# GDPHS_VGA_-_v2_2_1.net
KiCad netlist of a schematic drawn in EAGLE
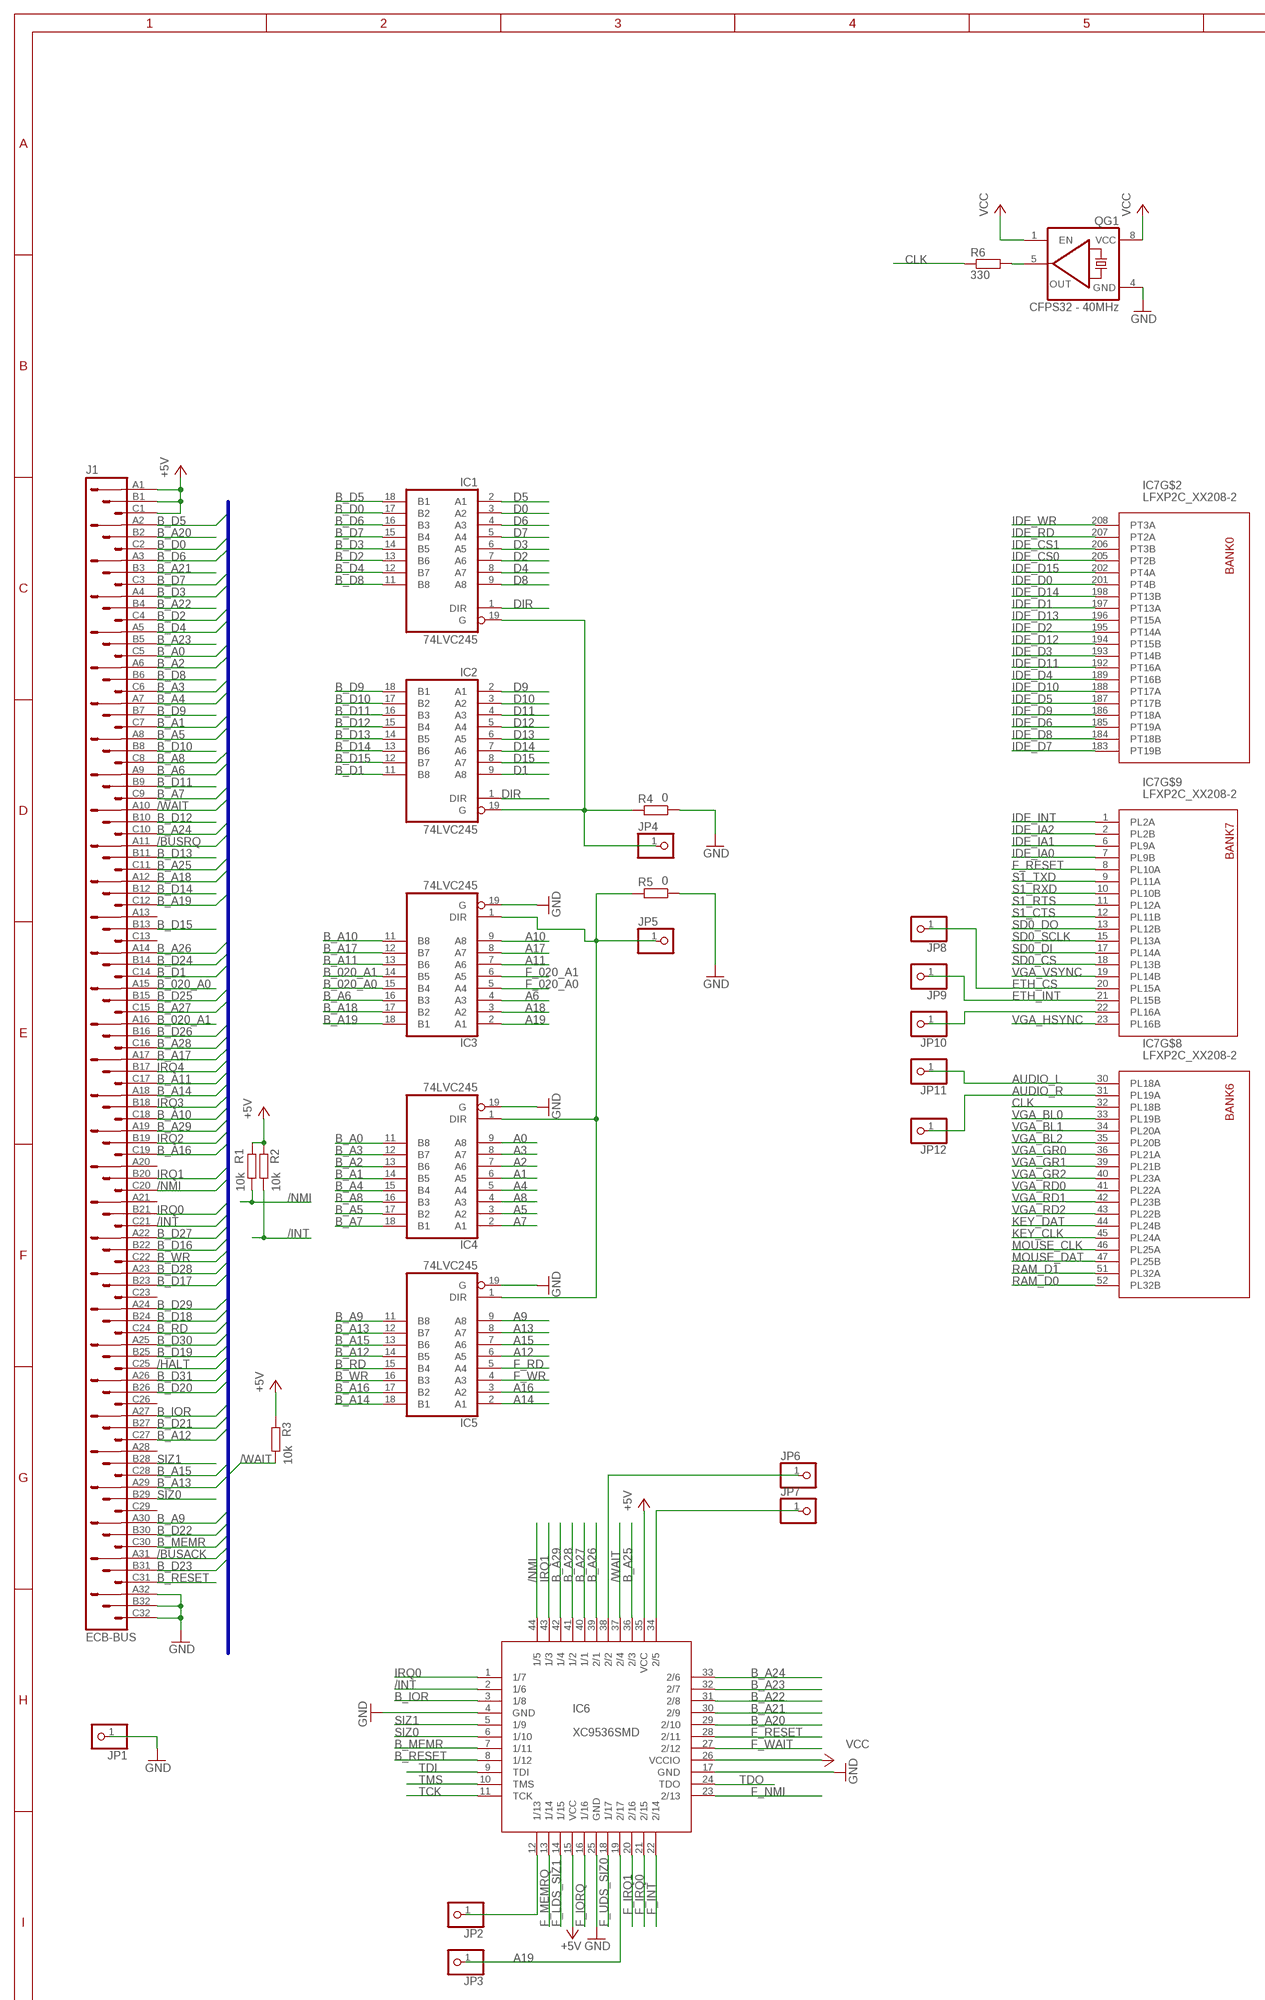
[diagram p0: schematic, sheet 1, part 1 of 2]
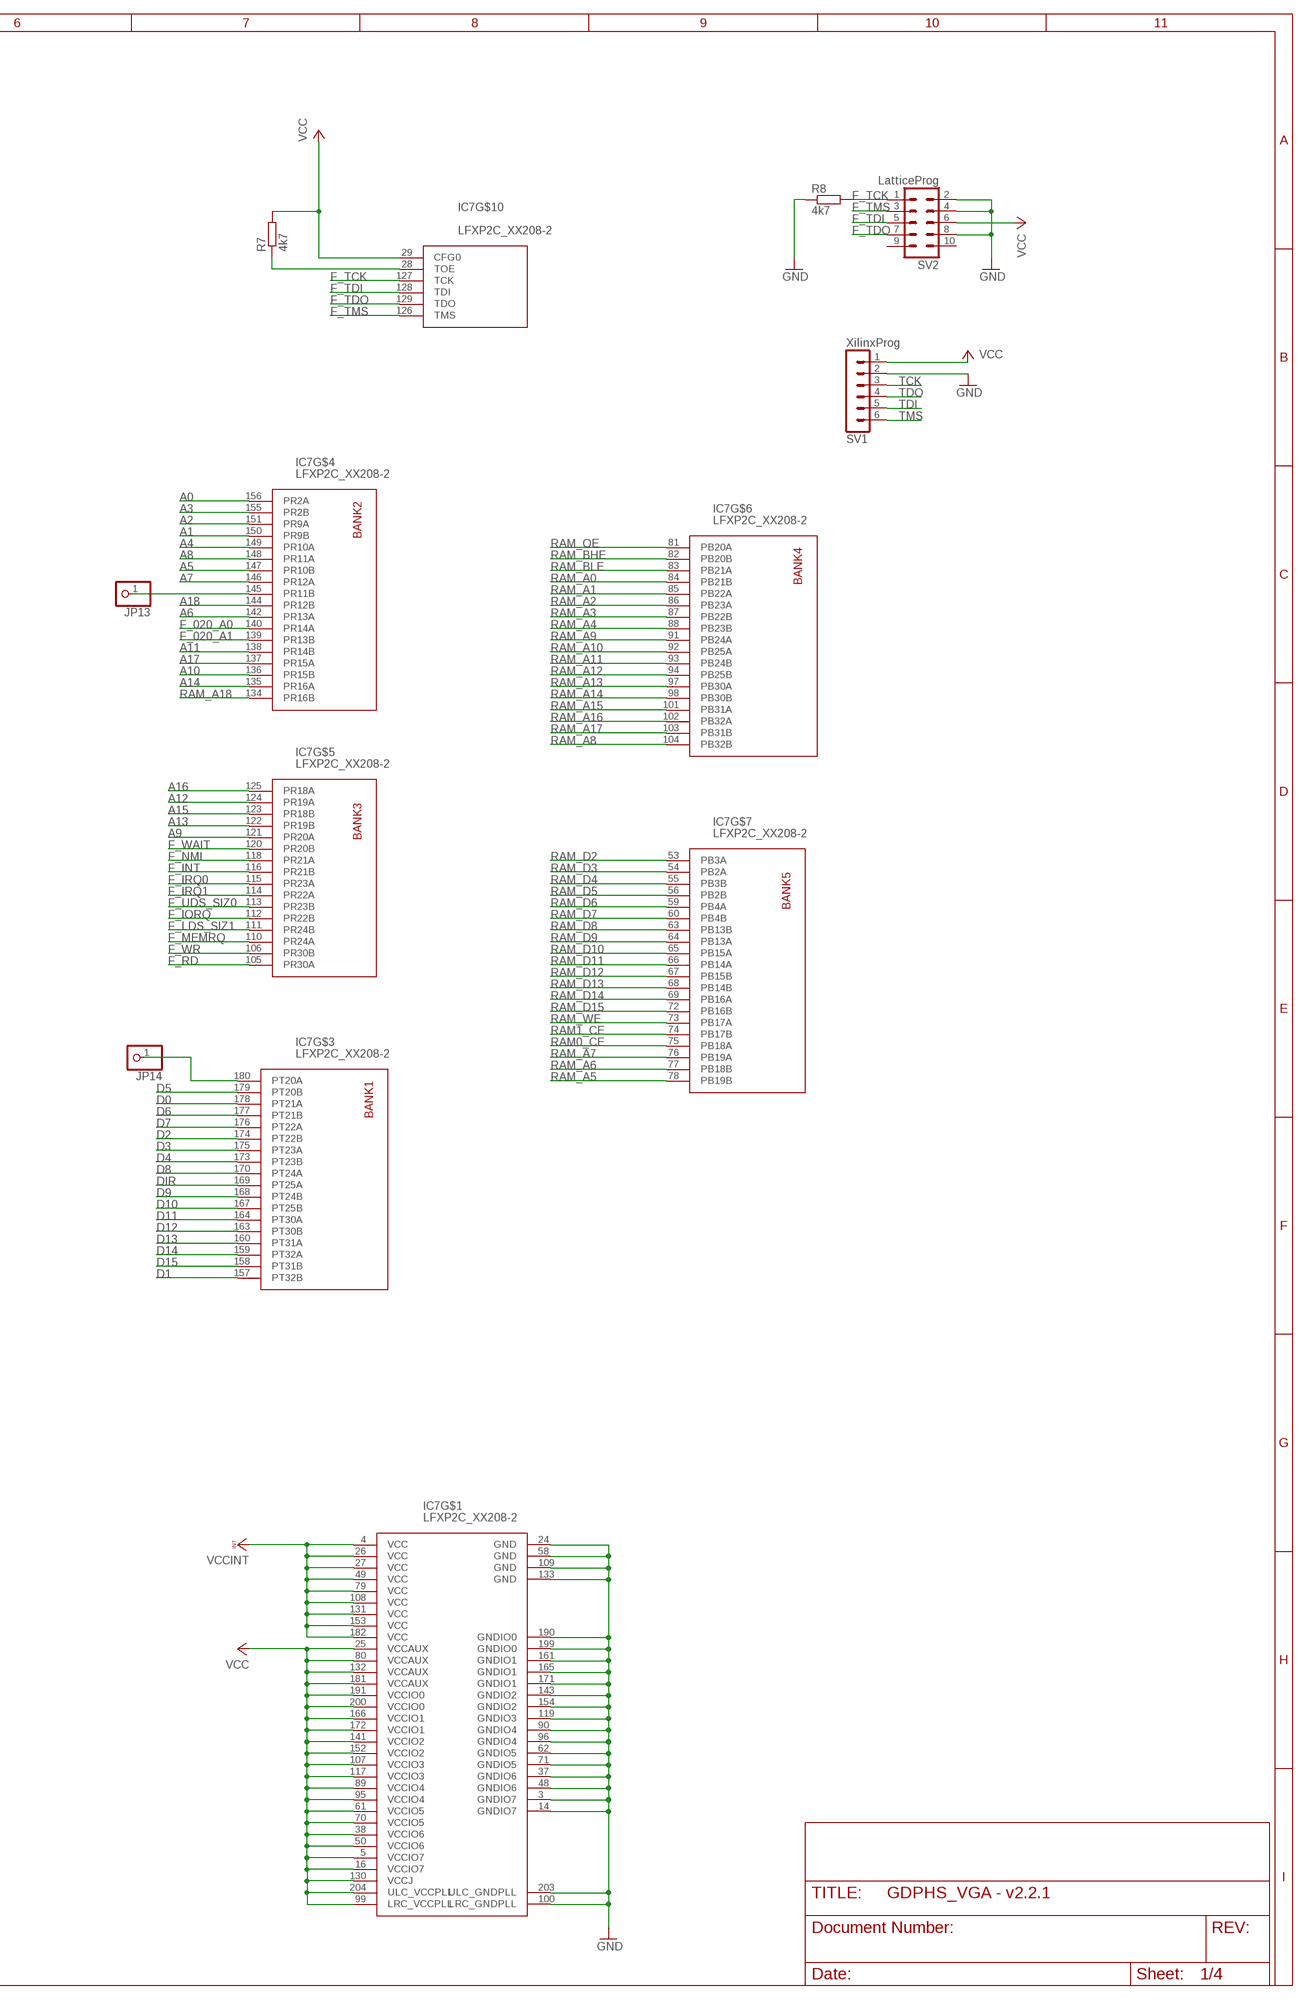
[diagram p1: schematic, sheet 1, part 2 of 2]
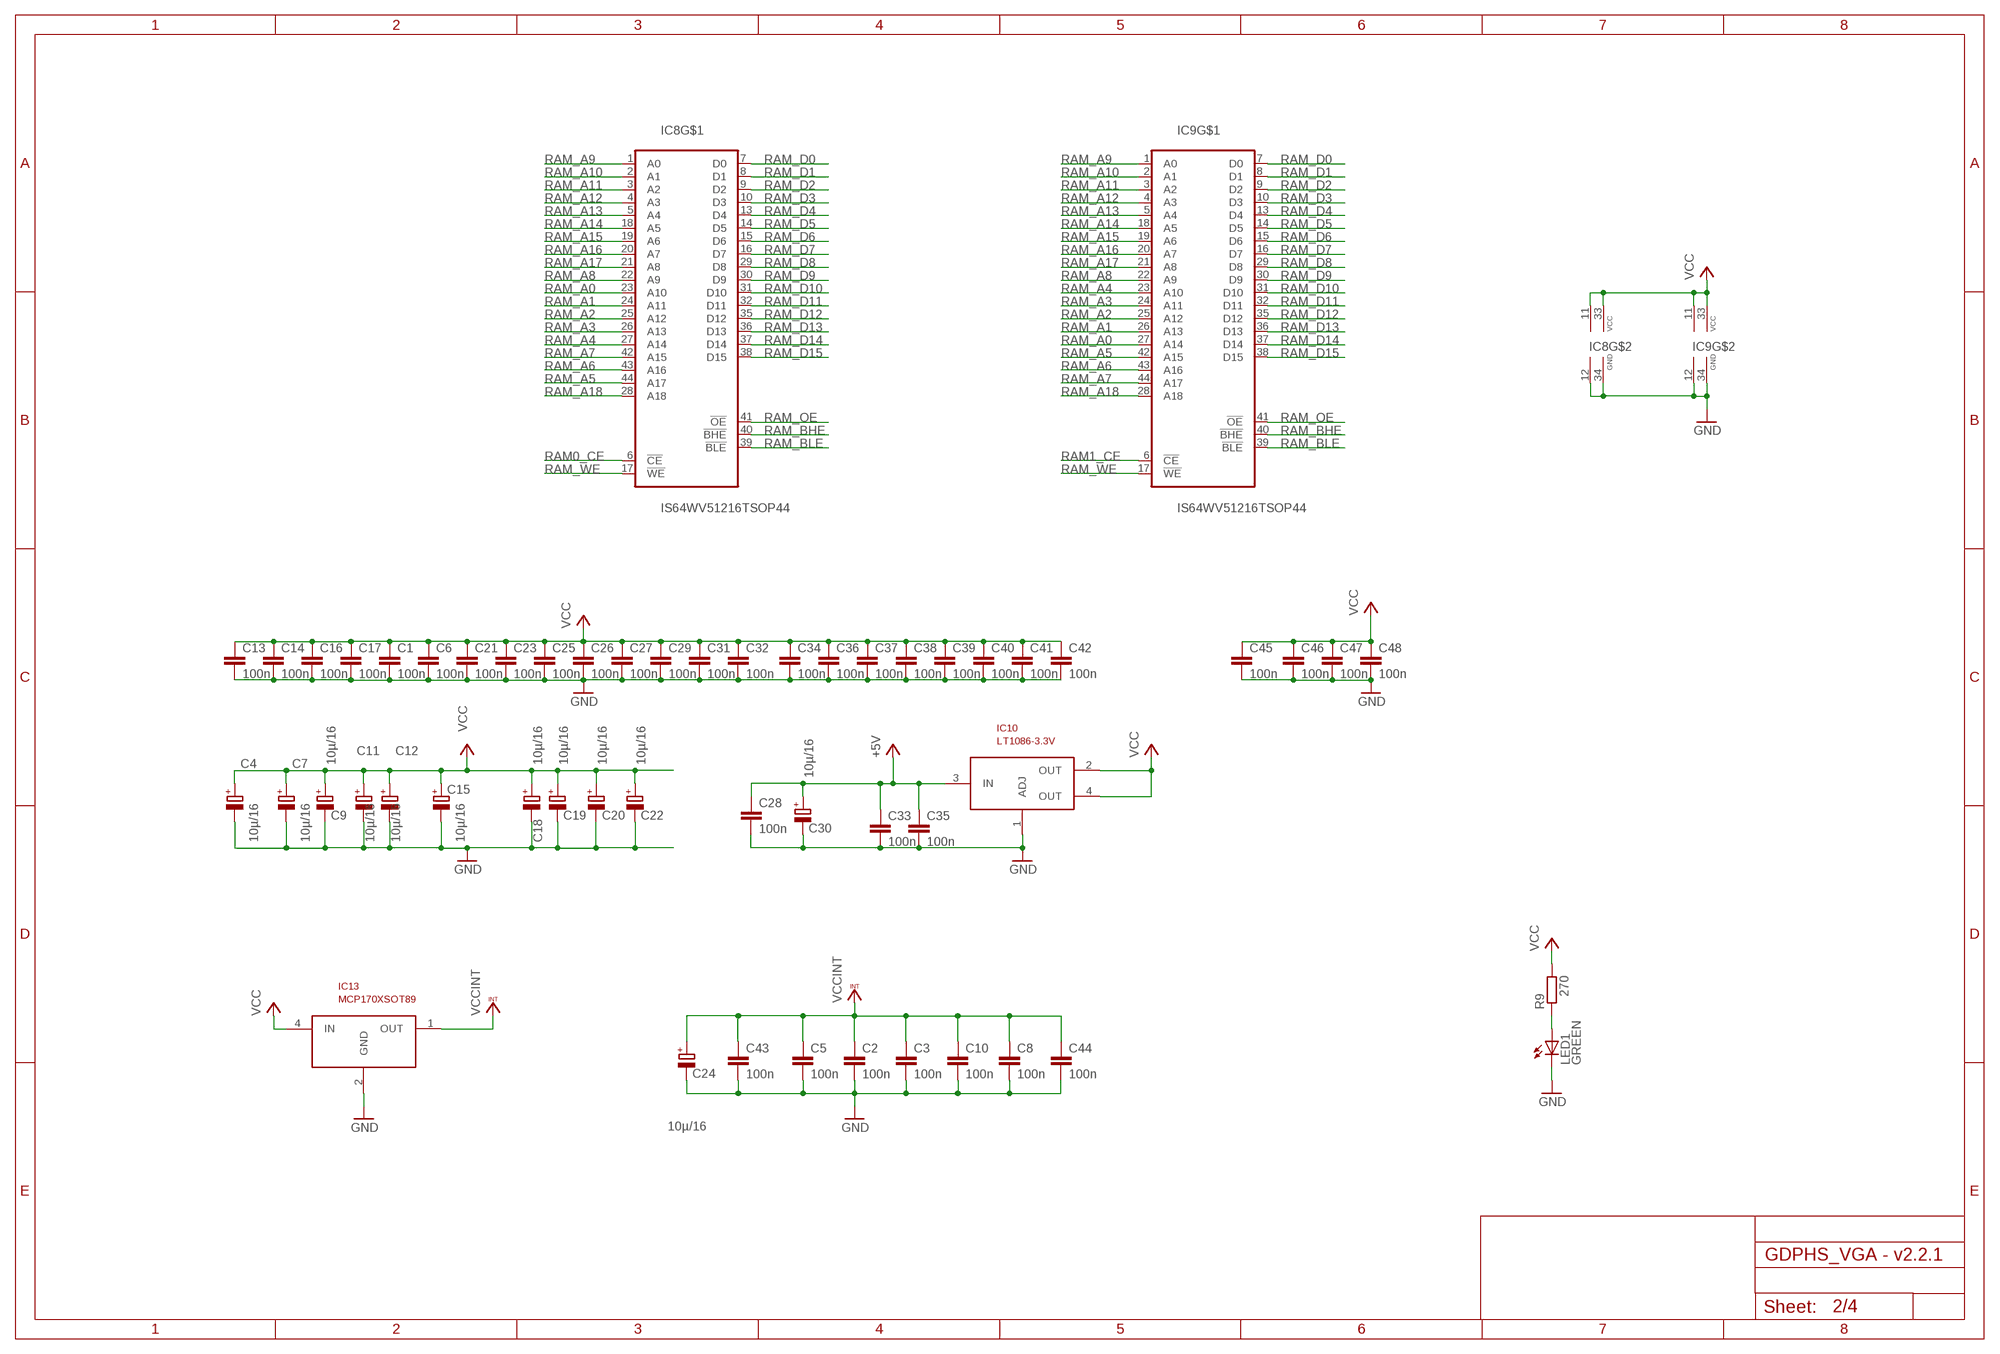
[diagram p2: schematic, sheet 2]
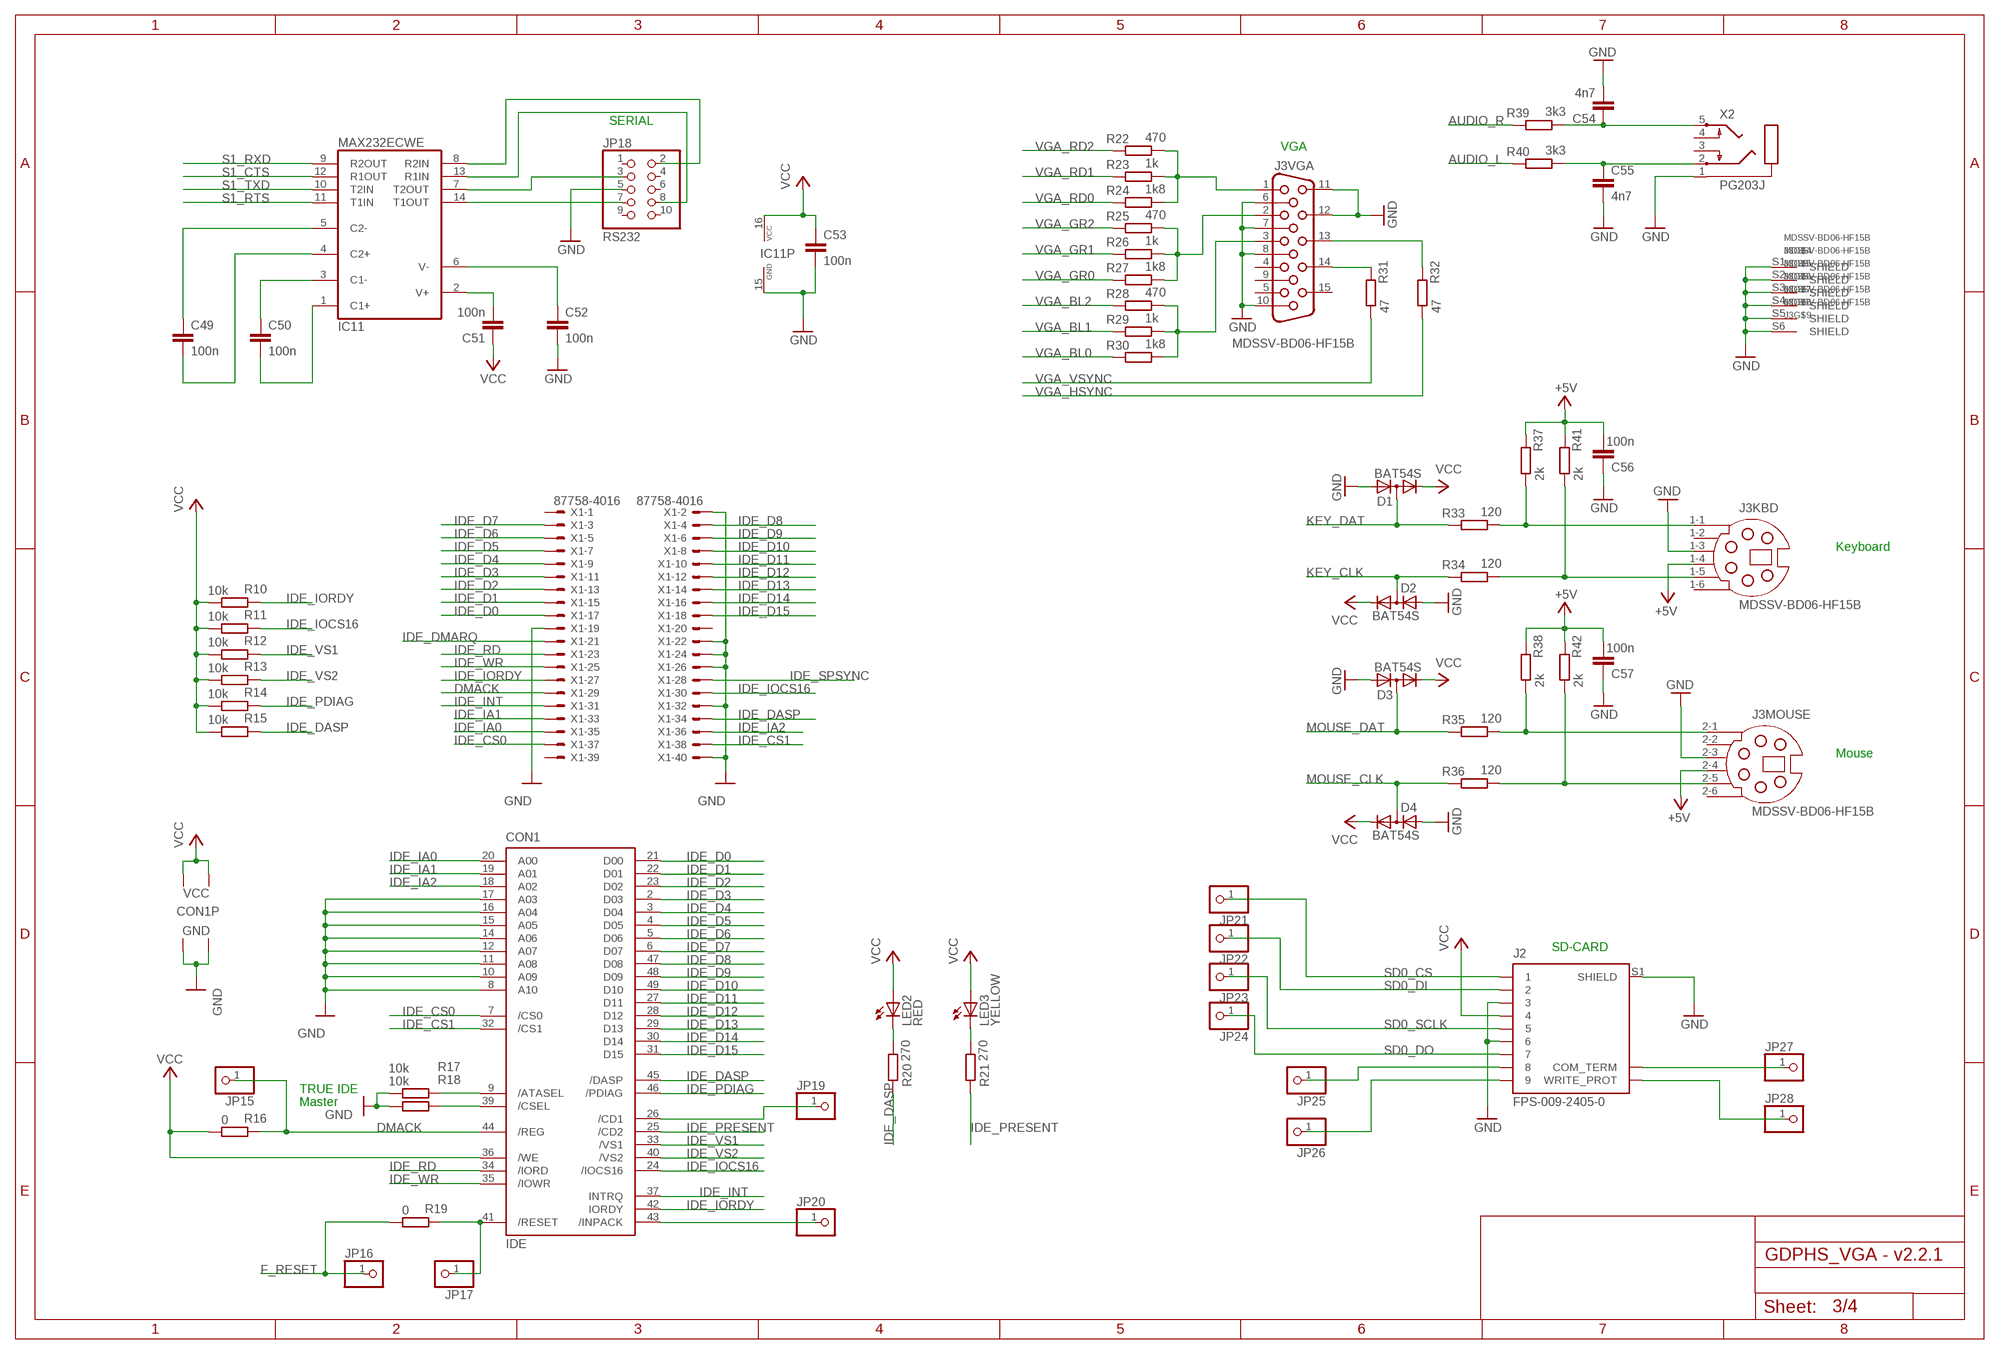
[diagram p3: schematic, sheet 3]
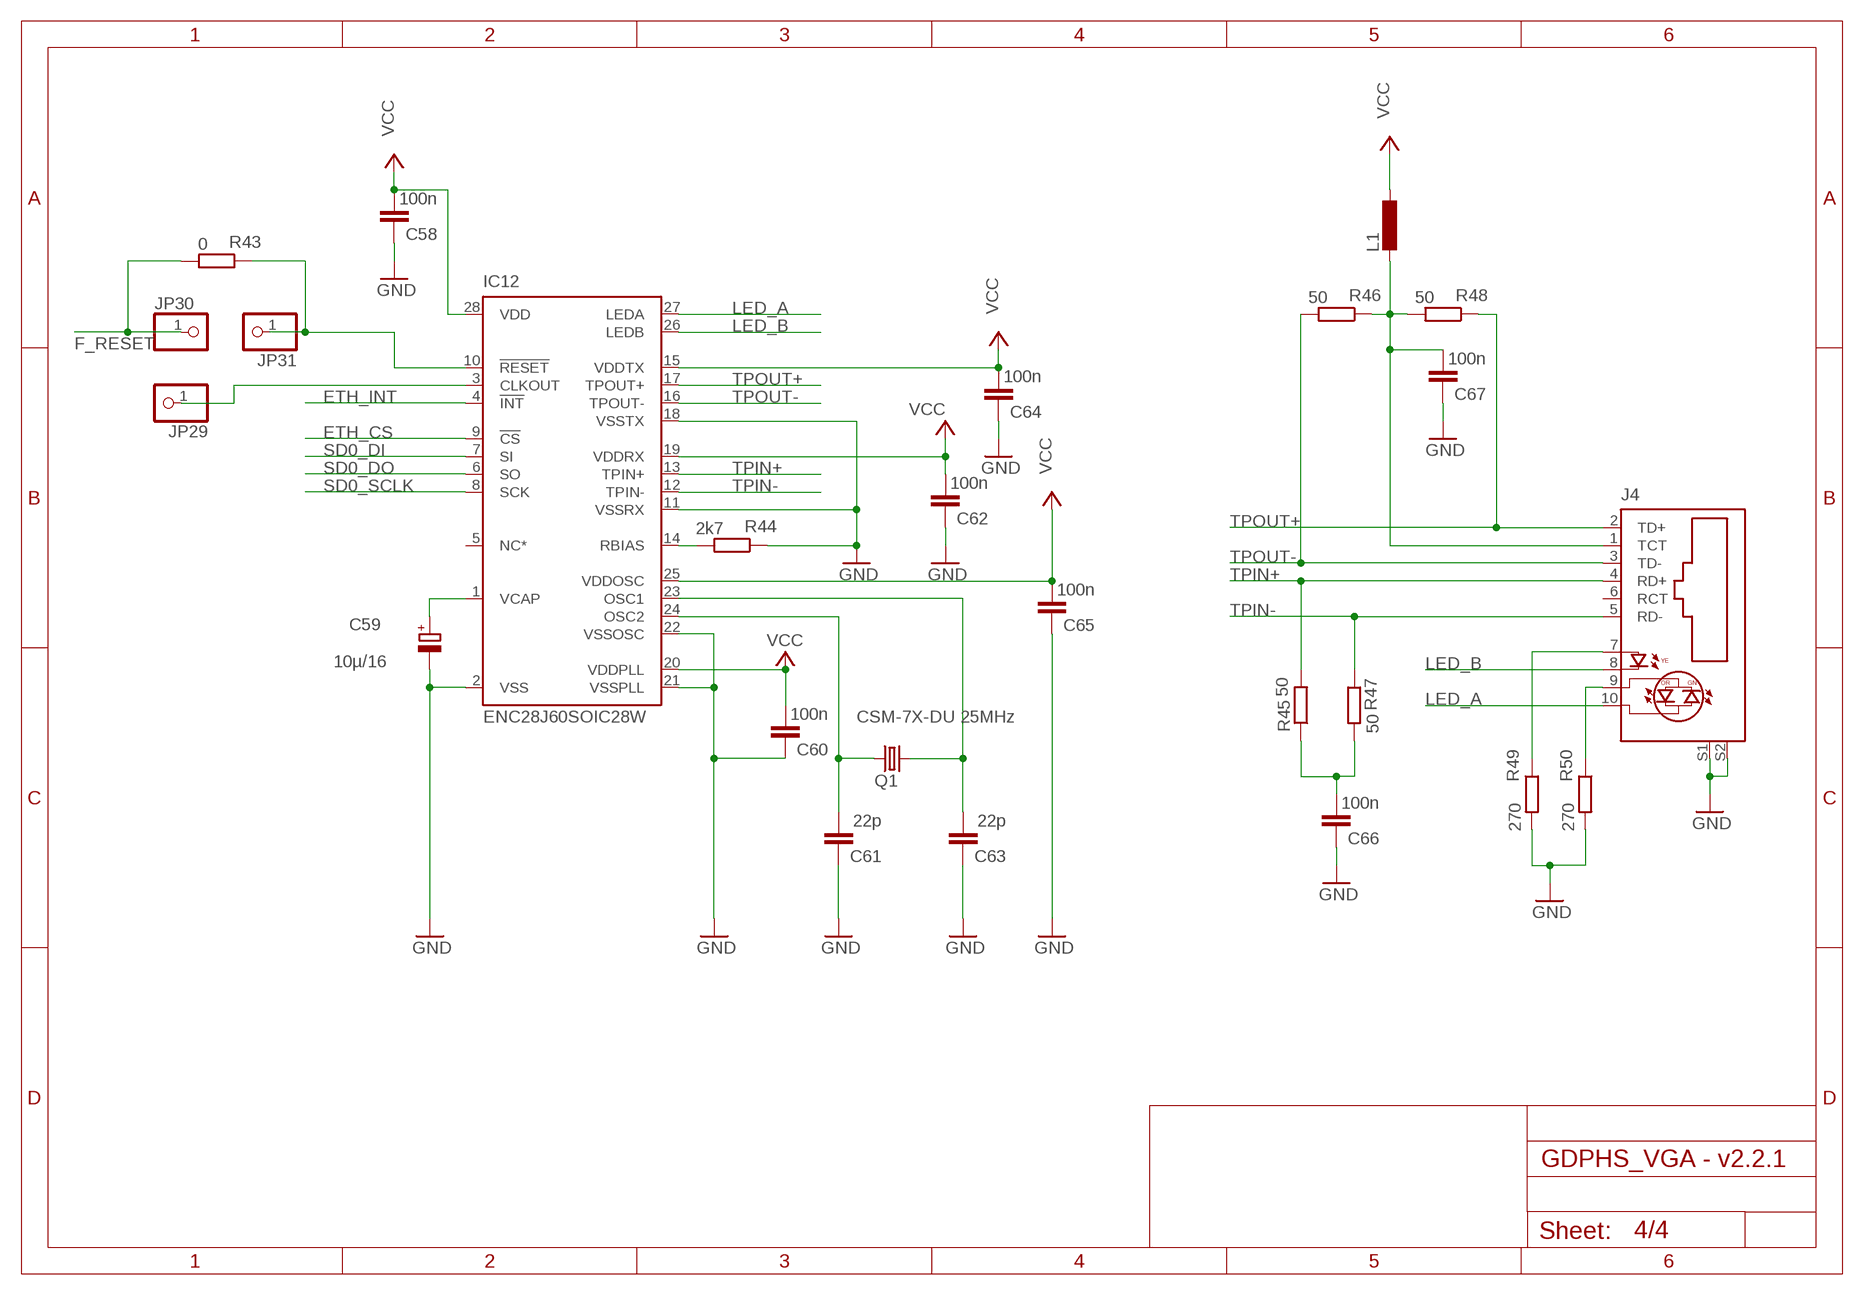
[diagram p4: schematic, sheet 4]

(export (version "E")
  (design (tool "Eeschema 10.0.6"))
  (components
    (comp (ref "C1")
      (value "100n")
      (footprint "eagle-import:C0805")
      (libsource (lib "eagle-import") (part "C-EUC0805"))
    )
    (comp (ref "C2")
      (value "100n")
      (footprint "eagle-import:C0805")
      (libsource (lib "eagle-import") (part "C-EUC0805"))
    )
    (comp (ref "C3")
      (value "100n")
      (footprint "eagle-import:C0805")
      (libsource (lib "eagle-import") (part "C-EUC0805"))
    )
    (comp (ref "C4")
      (value "10µ/16")
      (footprint "eagle-import:SMC_C")
      (libsource (lib "eagle-import") (part "CPOL-EUSMCC"))
    )
    (comp (ref "C5")
      (value "100n")
      (footprint "eagle-import:C0805")
      (libsource (lib "eagle-import") (part "C-EUC0805"))
    )
    (comp (ref "C6")
      (value "100n")
      (footprint "eagle-import:C0805")
      (libsource (lib "eagle-import") (part "C-EUC0805"))
    )
    (comp (ref "C7")
      (value "10µ/16")
      (footprint "eagle-import:SMC_C")
      (libsource (lib "eagle-import") (part "CPOL-EUSMCC"))
    )
    (comp (ref "C8")
      (value "100n")
      (footprint "eagle-import:C0805")
      (libsource (lib "eagle-import") (part "C-EUC0805"))
    )
    (comp (ref "C9")
      (value "10µ/16")
      (footprint "eagle-import:SMC_C")
      (libsource (lib "eagle-import") (part "CPOL-EUSMCC"))
    )
    (comp (ref "C10")
      (value "100n")
      (footprint "eagle-import:C0805")
      (libsource (lib "eagle-import") (part "C-EUC0805"))
    )
    (comp (ref "C11")
      (value "10µ/16")
      (footprint "eagle-import:SMC_C")
      (libsource (lib "eagle-import") (part "CPOL-EUSMCC"))
    )
    (comp (ref "C12")
      (value "10µ/16")
      (footprint "eagle-import:SMC_C")
      (libsource (lib "eagle-import") (part "CPOL-EUSMCC"))
    )
    (comp (ref "C13")
      (value "100n")
      (footprint "eagle-import:C0805")
      (libsource (lib "eagle-import") (part "C-EUC0805"))
    )
    (comp (ref "C14")
      (value "100n")
      (footprint "eagle-import:C0805")
      (libsource (lib "eagle-import") (part "C-EUC0805"))
    )
    (comp (ref "C15")
      (value "10µ/16")
      (footprint "eagle-import:SMC_C")
      (libsource (lib "eagle-import") (part "CPOL-EUSMCC"))
    )
    (comp (ref "C16")
      (value "100n")
      (footprint "eagle-import:C0805")
      (libsource (lib "eagle-import") (part "C-EUC0805"))
    )
    (comp (ref "C17")
      (value "100n")
      (footprint "eagle-import:C0805")
      (libsource (lib "eagle-import") (part "C-EUC0805"))
    )
    (comp (ref "C18")
      (value "10µ/16")
      (footprint "eagle-import:SMC_C")
      (libsource (lib "eagle-import") (part "CPOL-EUSMCC"))
    )
    (comp (ref "C19")
      (value "10µ/16")
      (footprint "eagle-import:SMC_C")
      (libsource (lib "eagle-import") (part "CPOL-EUSMCC"))
    )
    (comp (ref "C20")
      (value "10µ/16")
      (footprint "eagle-import:SMC_C")
      (libsource (lib "eagle-import") (part "CPOL-EUSMCC"))
    )
    (comp (ref "C21")
      (value "100n")
      (footprint "eagle-import:C0805")
      (libsource (lib "eagle-import") (part "C-EUC0805"))
    )
    (comp (ref "C22")
      (value "10µ/16")
      (footprint "eagle-import:SMC_C")
      (libsource (lib "eagle-import") (part "CPOL-EUSMCC"))
    )
    (comp (ref "C23")
      (value "100n")
      (footprint "eagle-import:C0805")
      (libsource (lib "eagle-import") (part "C-EUC0805"))
    )
    (comp (ref "C24")
      (value "10µ/16")
      (footprint "eagle-import:SMC_C")
      (libsource (lib "eagle-import") (part "CPOL-EUSMCC"))
    )
    (comp (ref "C25")
      (value "100n")
      (footprint "eagle-import:C0805")
      (libsource (lib "eagle-import") (part "C-EUC0805"))
    )
    (comp (ref "C26")
      (value "100n")
      (footprint "eagle-import:C0805")
      (libsource (lib "eagle-import") (part "C-EUC0805"))
    )
    (comp (ref "C27")
      (value "100n")
      (footprint "eagle-import:C0805")
      (libsource (lib "eagle-import") (part "C-EUC0805"))
    )
    (comp (ref "C28")
      (value "100n")
      (footprint "eagle-import:C0805")
      (libsource (lib "eagle-import") (part "C-EUC0805"))
    )
    (comp (ref "C29")
      (value "100n")
      (footprint "eagle-import:C0805")
      (libsource (lib "eagle-import") (part "C-EUC0805"))
    )
    (comp (ref "C30")
      (value "10µ/16")
      (footprint "eagle-import:SMC_C")
      (libsource (lib "eagle-import") (part "CPOL-EUSMCC"))
    )
    (comp (ref "C31")
      (value "100n")
      (footprint "eagle-import:C0805")
      (libsource (lib "eagle-import") (part "C-EUC0805"))
    )
    (comp (ref "C32")
      (value "100n")
      (footprint "eagle-import:C0805")
      (libsource (lib "eagle-import") (part "C-EUC0805"))
    )
    (comp (ref "C33")
      (value "100n")
      (footprint "eagle-import:C0805")
      (libsource (lib "eagle-import") (part "C-EUC0805"))
    )
    (comp (ref "C34")
      (value "100n")
      (footprint "eagle-import:C0805")
      (libsource (lib "eagle-import") (part "C-EUC0805"))
    )
    (comp (ref "C35")
      (value "100n")
      (footprint "eagle-import:C0805")
      (libsource (lib "eagle-import") (part "C-EUC0805"))
    )
    (comp (ref "C36")
      (value "100n")
      (footprint "eagle-import:C0805")
      (libsource (lib "eagle-import") (part "C-EUC0805"))
    )
    (comp (ref "C37")
      (value "100n")
      (footprint "eagle-import:C0805")
      (libsource (lib "eagle-import") (part "C-EUC0805"))
    )
    (comp (ref "C38")
      (value "100n")
      (footprint "eagle-import:C0805")
      (libsource (lib "eagle-import") (part "C-EUC0805"))
    )
    (comp (ref "C39")
      (value "100n")
      (footprint "eagle-import:C0805")
      (libsource (lib "eagle-import") (part "C-EUC0805"))
    )
    (comp (ref "C40")
      (value "100n")
      (footprint "eagle-import:C0805")
      (libsource (lib "eagle-import") (part "C-EUC0805"))
    )
    (comp (ref "C41")
      (value "100n")
      (footprint "eagle-import:C0805")
      (libsource (lib "eagle-import") (part "C-EUC0805"))
    )
    (comp (ref "C42")
      (value "100n")
      (footprint "eagle-import:C0805")
      (libsource (lib "eagle-import") (part "C-EUC0805"))
    )
    (comp (ref "C43")
      (value "100n")
      (footprint "eagle-import:C0805")
      (libsource (lib "eagle-import") (part "C-EUC0805"))
    )
    (comp (ref "C44")
      (value "100n")
      (footprint "eagle-import:C0805")
      (libsource (lib "eagle-import") (part "C-EUC0805"))
    )
    (comp (ref "C45")
      (value "100n")
      (footprint "eagle-import:C0805")
      (libsource (lib "eagle-import") (part "C-EUC0805"))
    )
    (comp (ref "C46")
      (value "100n")
      (footprint "eagle-import:C0805")
      (libsource (lib "eagle-import") (part "C-EUC0805"))
    )
    (comp (ref "C47")
      (value "100n")
      (footprint "eagle-import:C0805")
      (libsource (lib "eagle-import") (part "C-EUC0805"))
    )
    (comp (ref "C48")
      (value "100n")
      (footprint "eagle-import:C0805")
      (libsource (lib "eagle-import") (part "C-EUC0805"))
    )
    (comp (ref "IC8")
      (value "IS64WV51216TSOP44")
      (footprint "eagle-import:TSOP44-400")
      (fields
        (field (name "MF") "Cypress")
        (field (name "MPN") "CY7C1051DV33-10ZSXI")
        (field (name "OC_DIGIKEY") "428-3241-ND")
      )
      (libsource (lib "eagle-import") (part "IS64WV51216TSOP44"))
    )
    (comp (ref "IC9")
      (value "IS64WV51216TSOP44")
      (footprint "eagle-import:TSOP44-400")
      (fields
        (field (name "MF") "Cypress")
        (field (name "MPN") "CY7C1051DV33-10ZSXI")
        (field (name "OC_DIGIKEY") "428-3241-ND")
      )
      (libsource (lib "eagle-import") (part "IS64WV51216TSOP44"))
    )
    (comp (ref "IC10")
      (value "LT1086-3.3V")
      (footprint "eagle-import:MDD")
      (fields (field (name "MF") "Linear Technology") (field (name "MPN") "LT1086CM-3.3#PBF"))
      (libsource (lib "eagle-import") (part "LT1086"))
    )
    (comp (ref "IC13")
      (value "MCP170XSOT89")
      (footprint "eagle-import:SOT89-W")
      (libsource (lib "eagle-import") (part "MCP170XSOT89"))
    )
    (comp (ref "LED1")
      (value "GREEN")
      (footprint "eagle-import:CHIPLED_0805")
      (libsource (lib "eagle-import") (part "LEDCHIPLED_0805"))
    )
    (comp (ref "R9")
      (value "270")
      (footprint "eagle-import:M0805")
      (libsource (lib "eagle-import") (part "R-EU_M0805"))
    )
    (comp (ref "C58")
      (value "100n")
      (footprint "eagle-import:C0805")
      (libsource (lib "eagle-import") (part "C-EUC0805"))
    )
    (comp (ref "C59")
      (value "10µ/16")
      (footprint "eagle-import:SMC_C")
      (libsource (lib "eagle-import") (part "CPOL-EUSMCC"))
    )
    (comp (ref "C60")
      (value "100n")
      (footprint "eagle-import:C0805")
      (libsource (lib "eagle-import") (part "C-EUC0805"))
    )
    (comp (ref "C61")
      (value "22p")
      (footprint "eagle-import:C0805")
      (libsource (lib "eagle-import") (part "C-EUC0805"))
    )
    (comp (ref "C62")
      (value "100n")
      (footprint "eagle-import:C0805")
      (libsource (lib "eagle-import") (part "C-EUC0805"))
    )
    (comp (ref "C63")
      (value "22p")
      (footprint "eagle-import:C0805")
      (libsource (lib "eagle-import") (part "C-EUC0805"))
    )
    (comp (ref "C64")
      (value "100n")
      (footprint "eagle-import:C0805")
      (libsource (lib "eagle-import") (part "C-EUC0805"))
    )
    (comp (ref "C65")
      (value "100n")
      (footprint "eagle-import:C0805")
      (libsource (lib "eagle-import") (part "C-EUC0805"))
    )
    (comp (ref "C66")
      (value "100n")
      (footprint "eagle-import:C0805")
      (libsource (lib "eagle-import") (part "C-EUC0805"))
    )
    (comp (ref "C67")
      (value "100n")
      (footprint "eagle-import:C0805")
      (libsource (lib "eagle-import") (part "C-EUC0805"))
    )
    (comp (ref "IC12")
      (value "ENC28J60SOIC28W")
      (footprint "eagle-import:SO28W")
      (fields (field (name "MF") "MICROCHIP"))
      (libsource (lib "eagle-import") (part "ENC28J60SOIC28W"))
    )
    (comp (ref "J4")
      (value "08B0-1X1T-36-F08B0-1X1T-36-F")
      (footprint "eagle-import:08B0-1X1T-36-F")
      (fields (field (name "MF") "Bel Stewart") (field (name "MPN") "08B0-1X1T-36-F"))
      (libsource (lib "eagle-import") (part "08B0-1X1T-36-F08B0-1X1T-36-F"))
    )
    (comp (ref "JP29")
      (value "PINHD-1X1")
      (footprint "eagle-import:1X01")
      (libsource (lib "eagle-import") (part "PINHD-1X1"))
    )
    (comp (ref "JP30")
      (value "PINHD-1X1")
      (footprint "eagle-import:1X01")
      (libsource (lib "eagle-import") (part "PINHD-1X1"))
    )
    (comp (ref "JP31")
      (value "PINHD-1X1")
      (footprint "eagle-import:1X01")
      (libsource (lib "eagle-import") (part "PINHD-1X1"))
    )
    (comp (ref "L1")
      (value "L-EUL1206")
      (footprint "eagle-import:L1206")
      (fields (field (name "MF") "Steward") (field (name "MPN") "MI1210K600R-10"))
      (libsource (lib "eagle-import") (part "L-EUL1206"))
    )
    (comp (ref "Q1")
      (value "CSM-7X-DU 25MHz")
      (footprint "eagle-import:CSM-7X-DU")
      (fields (field (name "MF") "CITIZEN") (field (name "MPN") "CS10-25.000MABJTR"))
      (libsource (lib "eagle-import") (part "CSM-7X-DU"))
    )
    (comp (ref "R43")
      (value "0")
      (footprint "eagle-import:M0805")
      (libsource (lib "eagle-import") (part "R-EU_M0805"))
    )
    (comp (ref "R44")
      (value "2k7")
      (footprint "eagle-import:M0805")
      (libsource (lib "eagle-import") (part "R-EU_M0805"))
    )
    (comp (ref "R45")
      (value "50")
      (footprint "eagle-import:M0805")
      (libsource (lib "eagle-import") (part "R-EU_M0805"))
    )
    (comp (ref "R46")
      (value "50")
      (footprint "eagle-import:M0805")
      (libsource (lib "eagle-import") (part "R-EU_M0805"))
    )
    (comp (ref "R47")
      (value "50")
      (footprint "eagle-import:M0805")
      (libsource (lib "eagle-import") (part "R-EU_M0805"))
    )
    (comp (ref "R48")
      (value "50")
      (footprint "eagle-import:M0805")
      (libsource (lib "eagle-import") (part "R-EU_M0805"))
    )
    (comp (ref "R49")
      (value "270")
      (footprint "eagle-import:M0805")
      (libsource (lib "eagle-import") (part "R-EU_M0805"))
    )
    (comp (ref "R50")
      (value "270")
      (footprint "eagle-import:M0805")
      (libsource (lib "eagle-import") (part "R-EU_M0805"))
    )
    (comp (ref "C49")
      (value "100n")
      (footprint "eagle-import:C0805")
      (libsource (lib "eagle-import") (part "C-EUC0805"))
    )
    (comp (ref "C50")
      (value "100n")
      (footprint "eagle-import:C0805")
      (libsource (lib "eagle-import") (part "C-EUC0805"))
    )
    (comp (ref "C51")
      (value "100n")
      (footprint "eagle-import:C0805")
      (libsource (lib "eagle-import") (part "C-EUC0805"))
    )
    (comp (ref "C52")
      (value "100n")
      (footprint "eagle-import:C0805")
      (libsource (lib "eagle-import") (part "C-EUC0805"))
    )
    (comp (ref "C53")
      (value "100n")
      (footprint "eagle-import:C0805")
      (libsource (lib "eagle-import") (part "C-EUC0805"))
    )
    (comp (ref "C54")
      (value "4n7")
      (footprint "eagle-import:C0805")
      (libsource (lib "eagle-import") (part "C-EUC0805"))
    )
    (comp (ref "C55")
      (value "4n7")
      (footprint "eagle-import:C0805")
      (libsource (lib "eagle-import") (part "C-EUC0805"))
    )
    (comp (ref "C56")
      (value "100n")
      (footprint "eagle-import:C0805")
      (libsource (lib "eagle-import") (part "C-EUC0805"))
    )
    (comp (ref "C57")
      (value "100n")
      (footprint "eagle-import:C0805")
      (libsource (lib "eagle-import") (part "C-EUC0805"))
    )
    (comp (ref "CON1")
      (value "IDE")
      (footprint "eagle-import:CF-050-P2-X03-10-DS-1")
      (fields (field (name "MF") "Yamaichi") (field (name "MPN") "CF-050P2-103-10-DS1"))
      (libsource (lib "eagle-import") (part "CF-CARD-IDE_MODEYAMAI-CF-CARD-I-II"))
    )
    (comp (ref "D1")
      (value "BAT54S")
      (footprint "eagle-import:SOT23")
      (libsource (lib "eagle-import") (part "DIODE_2CACA-SOT23"))
    )
    (comp (ref "D2")
      (value "BAT54S")
      (footprint "eagle-import:SOT23")
      (libsource (lib "eagle-import") (part "DIODE_2CACA-SOT23"))
    )
    (comp (ref "D3")
      (value "BAT54S")
      (footprint "eagle-import:SOT23")
      (libsource (lib "eagle-import") (part "DIODE_2CACA-SOT23"))
    )
    (comp (ref "D4")
      (value "BAT54S")
      (footprint "eagle-import:SOT23")
      (libsource (lib "eagle-import") (part "DIODE_2CACA-SOT23"))
    )
    (comp (ref "IC11")
      (value "MAX232ECWE")
      (footprint "eagle-import:SO16L")
      (fields (field (name "MF") "MAXIM") (field (name "MPN") "MAX232ECWE+"))
      (libsource (lib "eagle-import") (part "MAX232ECWE"))
    )
    (comp (ref "J2")
      (value "FPS-009-2405-0")
      (footprint "eagle-import:FPS-009-2405-0")
      (fields (field (name "MF") "Yamaichi"))
      (libsource (lib "eagle-import") (part "FPS-009-2405-0"))
    )
    (comp (ref "J3")
      (value "MDSSV-BD06-HF15B")
      (footprint "eagle-import:MDSSV-BD06-HF15-B")
      (fields (field (name "MF") "Norcomp Inc.") (field (name "MPN") "999-H15-PS2L571"))
      (libsource (lib "eagle-import") (part "MDSSV-BD06-HF15B"))
    )
    (comp (ref "JP15")
      (value "PINHD-1X1")
      (footprint "eagle-import:1X01")
      (libsource (lib "eagle-import") (part "PINHD-1X1"))
    )
    (comp (ref "JP16")
      (value "PINHD-1X1")
      (footprint "eagle-import:1X01")
      (libsource (lib "eagle-import") (part "PINHD-1X1"))
    )
    (comp (ref "JP17")
      (value "PINHD-1X1")
      (footprint "eagle-import:1X01")
      (libsource (lib "eagle-import") (part "PINHD-1X1"))
    )
    (comp (ref "JP18")
      (value "RS232")
      (footprint "eagle-import:2X05")
      (libsource (lib "eagle-import") (part "PINHD-2X5"))
    )
    (comp (ref "JP19")
      (value "PINHD-1X1")
      (footprint "eagle-import:1X01")
      (libsource (lib "eagle-import") (part "PINHD-1X1"))
    )
    (comp (ref "JP20")
      (value "PINHD-1X1")
      (footprint "eagle-import:1X01")
      (libsource (lib "eagle-import") (part "PINHD-1X1"))
    )
    (comp (ref "JP21")
      (value "PINHD-1X1")
      (footprint "eagle-import:1X01")
      (libsource (lib "eagle-import") (part "PINHD-1X1"))
    )
    (comp (ref "JP22")
      (value "PINHD-1X1")
      (footprint "eagle-import:1X01")
      (libsource (lib "eagle-import") (part "PINHD-1X1"))
    )
    (comp (ref "JP23")
      (value "PINHD-1X1")
      (footprint "eagle-import:1X01")
      (libsource (lib "eagle-import") (part "PINHD-1X1"))
    )
    (comp (ref "JP24")
      (value "PINHD-1X1")
      (footprint "eagle-import:1X01")
      (libsource (lib "eagle-import") (part "PINHD-1X1"))
    )
    (comp (ref "JP25")
      (value "PINHD-1X1")
      (footprint "eagle-import:1X01")
      (libsource (lib "eagle-import") (part "PINHD-1X1"))
    )
    (comp (ref "JP26")
      (value "PINHD-1X1")
      (footprint "eagle-import:1X01")
      (libsource (lib "eagle-import") (part "PINHD-1X1"))
    )
    (comp (ref "JP27")
      (value "PINHD-1X1")
      (footprint "eagle-import:1X01")
      (libsource (lib "eagle-import") (part "PINHD-1X1"))
    )
    (comp (ref "JP28")
      (value "PINHD-1X1")
      (footprint "eagle-import:1X01")
      (libsource (lib "eagle-import") (part "PINHD-1X1"))
    )
    (comp (ref "LED2")
      (value "RED")
      (footprint "eagle-import:CHIPLED_0805")
      (libsource (lib "eagle-import") (part "LEDCHIPLED_0805"))
    )
    (comp (ref "LED3")
      (value "YELLOW")
      (footprint "eagle-import:CHIPLED_0805")
      (libsource (lib "eagle-import") (part "LEDCHIPLED_0805"))
    )
    (comp (ref "R10")
      (value "10k")
      (footprint "eagle-import:M0805")
      (libsource (lib "eagle-import") (part "R-EU_M0805"))
    )
    (comp (ref "R11")
      (value "10k")
      (footprint "eagle-import:M0805")
      (libsource (lib "eagle-import") (part "R-EU_M0805"))
    )
    (comp (ref "R12")
      (value "10k")
      (footprint "eagle-import:M0805")
      (libsource (lib "eagle-import") (part "R-EU_M0805"))
    )
    (comp (ref "R13")
      (value "10k")
      (footprint "eagle-import:M0805")
      (libsource (lib "eagle-import") (part "R-EU_M0805"))
    )
    (comp (ref "R14")
      (value "10k")
      (footprint "eagle-import:M0805")
      (libsource (lib "eagle-import") (part "R-EU_M0805"))
    )
    (comp (ref "R15")
      (value "10k")
      (footprint "eagle-import:M0805")
      (libsource (lib "eagle-import") (part "R-EU_M0805"))
    )
    (comp (ref "R16")
      (value "0")
      (footprint "eagle-import:M0805")
      (libsource (lib "eagle-import") (part "R-EU_M0805"))
    )
    (comp (ref "R17")
      (value "10k")
      (footprint "eagle-import:M0805")
      (libsource (lib "eagle-import") (part "R-EU_M0805"))
    )
    (comp (ref "R18")
      (value "10k")
      (footprint "eagle-import:M0805")
      (libsource (lib "eagle-import") (part "R-EU_M0805"))
    )
    (comp (ref "R19")
      (value "0")
      (footprint "eagle-import:M0805")
      (libsource (lib "eagle-import") (part "R-EU_M0805"))
    )
    (comp (ref "R20")
      (value "270")
      (footprint "eagle-import:M0805")
      (libsource (lib "eagle-import") (part "R-EU_M0805"))
    )
    (comp (ref "R21")
      (value "270")
      (footprint "eagle-import:M0805")
      (libsource (lib "eagle-import") (part "R-EU_M0805"))
    )
    (comp (ref "R22")
      (value "470")
      (footprint "eagle-import:M0805")
      (libsource (lib "eagle-import") (part "R-EU_M0805"))
    )
    (comp (ref "R23")
      (value "1k")
      (footprint "eagle-import:M0805")
      (libsource (lib "eagle-import") (part "R-EU_M0805"))
    )
    (comp (ref "R24")
      (value "1k8")
      (footprint "eagle-import:M0805")
      (libsource (lib "eagle-import") (part "R-EU_M0805"))
    )
    (comp (ref "R25")
      (value "470")
      (footprint "eagle-import:M0805")
      (libsource (lib "eagle-import") (part "R-EU_M0805"))
    )
    (comp (ref "R26")
      (value "1k")
      (footprint "eagle-import:M0805")
      (libsource (lib "eagle-import") (part "R-EU_M0805"))
    )
    (comp (ref "R27")
      (value "1k8")
      (footprint "eagle-import:M0805")
      (libsource (lib "eagle-import") (part "R-EU_M0805"))
    )
    (comp (ref "R28")
      (value "470")
      (footprint "eagle-import:M0805")
      (libsource (lib "eagle-import") (part "R-EU_M0805"))
    )
    (comp (ref "R29")
      (value "1k")
      (footprint "eagle-import:M0805")
      (libsource (lib "eagle-import") (part "R-EU_M0805"))
    )
    (comp (ref "R30")
      (value "1k8")
      (footprint "eagle-import:M0805")
      (libsource (lib "eagle-import") (part "R-EU_M0805"))
    )
    (comp (ref "R31")
      (value "47")
      (footprint "eagle-import:M0805")
      (libsource (lib "eagle-import") (part "R-EU_M0805"))
    )
    (comp (ref "R32")
      (value "47")
      (footprint "eagle-import:M0805")
      (libsource (lib "eagle-import") (part "R-EU_M0805"))
    )
    (comp (ref "R33")
      (value "120")
      (footprint "eagle-import:M0805")
      (libsource (lib "eagle-import") (part "R-EU_M0805"))
    )
    (comp (ref "R34")
      (value "120")
      (footprint "eagle-import:M0805")
      (libsource (lib "eagle-import") (part "R-EU_M0805"))
    )
    (comp (ref "R35")
      (value "120")
      (footprint "eagle-import:M0805")
      (libsource (lib "eagle-import") (part "R-EU_M0805"))
    )
    (comp (ref "R36")
      (value "120")
      (footprint "eagle-import:M0805")
      (libsource (lib "eagle-import") (part "R-EU_M0805"))
    )
    (comp (ref "R37")
      (value "2k")
      (footprint "eagle-import:M0805")
      (libsource (lib "eagle-import") (part "R-EU_M0805"))
    )
    (comp (ref "R38")
      (value "2k")
      (footprint "eagle-import:M0805")
      (libsource (lib "eagle-import") (part "R-EU_M0805"))
    )
    (comp (ref "R39")
      (value "3k3")
      (footprint "eagle-import:M0805")
      (libsource (lib "eagle-import") (part "R-EU_M0805"))
    )
    (comp (ref "R40")
      (value "3k3")
      (footprint "eagle-import:M0805")
      (libsource (lib "eagle-import") (part "R-EU_M0805"))
    )
    (comp (ref "R41")
      (value "2k")
      (footprint "eagle-import:M0805")
      (libsource (lib "eagle-import") (part "R-EU_M0805"))
    )
    (comp (ref "R42")
      (value "2k")
      (footprint "eagle-import:M0805")
      (libsource (lib "eagle-import") (part "R-EU_M0805"))
    )
    (comp (ref "X1")
      (value "87758-4016")
      (footprint "eagle-import:87758-4016")
      (libsource (lib "eagle-import") (part "87758-4016"))
    )
    (comp (ref "X2")
      (value "PG203J")
      (footprint "eagle-import:PG203J")
      (libsource (lib "eagle-import") (part "PG203J"))
    )
    (comp (ref "IC1")
      (value "74LVC245")
      (footprint "eagle-import:SO20W")
      (fields (field (name "MF") "Texas Instruments") (field (name "MPN") "SN74LVC245ADWR"))
      (libsource (lib "eagle-import") (part "74245DWLVC"))
    )
    (comp (ref "IC2")
      (value "74LVC245")
      (footprint "eagle-import:SO20W")
      (fields (field (name "MF") "Texas Instruments") (field (name "MPN") "SN74LVC245ADWR"))
      (libsource (lib "eagle-import") (part "74245DWLVC"))
    )
    (comp (ref "IC3")
      (value "74LVC245")
      (footprint "eagle-import:SO20W")
      (fields (field (name "MF") "Texas Instruments") (field (name "MPN") "SN74LVC245ADWR"))
      (libsource (lib "eagle-import") (part "74245DWLVC"))
    )
    (comp (ref "IC4")
      (value "74LVC245")
      (footprint "eagle-import:SO20W")
      (fields (field (name "MF") "Texas Instruments") (field (name "MPN") "SN74LVC245ADWR"))
      (libsource (lib "eagle-import") (part "74245DWLVC"))
    )
    (comp (ref "IC5")
      (value "74LVC245")
      (footprint "eagle-import:SO20W")
      (fields (field (name "MF") "Texas Instruments") (field (name "MPN") "SN74LVC245ADWR"))
      (libsource (lib "eagle-import") (part "74245DWLVC"))
    )
    (comp (ref "IC6")
      (value "XC9536SMD")
      (footprint "eagle-import:TQFP44")
      (libsource (lib "eagle-import") (part "XC9536SMD"))
    )
    (comp (ref "IC7")
      (value "LFXP2C_XX208-2")
      (footprint "eagle-import:PQFP_208")
      (fields
        (field (name "MF") "Lattice")
        (field (name "MPN") "LFXP2-8E-5QN208C")
        (field (name "OC_DIGIKEY") "220-1253-ND")
      )
      (libsource (lib "eagle-import") (part "LFXP2C_XX208-2"))
    )
    (comp (ref "J1")
      (value "ECB-BUS")
      (footprint "eagle-import:VG96K")
      (libsource (lib "eagle-import") (part "VG96K"))
    )
    (comp (ref "JP1")
      (value "PINHD-1X1")
      (footprint "eagle-import:1X01")
      (libsource (lib "eagle-import") (part "PINHD-1X1"))
    )
    (comp (ref "JP2")
      (value "PINHD-1X1")
      (footprint "eagle-import:1X01")
      (libsource (lib "eagle-import") (part "PINHD-1X1"))
    )
    (comp (ref "JP3")
      (value "PINHD-1X1")
      (footprint "eagle-import:1X01")
      (libsource (lib "eagle-import") (part "PINHD-1X1"))
    )
    (comp (ref "JP4")
      (value "PINHD-1X1")
      (footprint "eagle-import:1X01")
      (libsource (lib "eagle-import") (part "PINHD-1X1"))
    )
    (comp (ref "JP5")
      (value "PINHD-1X1")
      (footprint "eagle-import:1X01")
      (libsource (lib "eagle-import") (part "PINHD-1X1"))
    )
    (comp (ref "JP6")
      (value "PINHD-1X1")
      (footprint "eagle-import:1X01")
      (libsource (lib "eagle-import") (part "PINHD-1X1"))
    )
    (comp (ref "JP7")
      (value "PINHD-1X1")
      (footprint "eagle-import:1X01")
      (libsource (lib "eagle-import") (part "PINHD-1X1"))
    )
    (comp (ref "JP8")
      (value "PINHD-1X1")
      (footprint "eagle-import:1X01")
      (libsource (lib "eagle-import") (part "PINHD-1X1"))
    )
    (comp (ref "JP9")
      (value "PINHD-1X1")
      (footprint "eagle-import:1X01")
      (libsource (lib "eagle-import") (part "PINHD-1X1"))
    )
    (comp (ref "JP10")
      (value "PINHD-1X1")
      (footprint "eagle-import:1X01")
      (libsource (lib "eagle-import") (part "PINHD-1X1"))
    )
    (comp (ref "JP11")
      (value "PINHD-1X1")
      (footprint "eagle-import:1X01")
      (libsource (lib "eagle-import") (part "PINHD-1X1"))
    )
    (comp (ref "JP12")
      (value "PINHD-1X1")
      (footprint "eagle-import:1X01")
      (libsource (lib "eagle-import") (part "PINHD-1X1"))
    )
    (comp (ref "JP13")
      (value "PINHD-1X1")
      (footprint "eagle-import:1X01")
      (libsource (lib "eagle-import") (part "PINHD-1X1"))
    )
    (comp (ref "JP14")
      (value "PINHD-1X1")
      (footprint "eagle-import:1X01")
      (libsource (lib "eagle-import") (part "PINHD-1X1"))
    )
    (comp (ref "QG1")
      (value "CFPS32 - 40MHz")
      (footprint "eagle-import:CFPS7X")
      (fields
        (field (name "MF") "IQD FREQUENCY PRODUCTS")
        (field (name "MPN") "LF SPXO018042 - QUARZ, 40MHZ, 15PF, SMD")
      )
      (libsource (lib "eagle-import") (part "CRYSTAL_RESONATORCFPS7X"))
    )
    (comp (ref "R1")
      (value "10k")
      (footprint "eagle-import:M0805")
      (libsource (lib "eagle-import") (part "R-EU_M0805"))
    )
    (comp (ref "R2")
      (value "10k")
      (footprint "eagle-import:M0805")
      (libsource (lib "eagle-import") (part "R-EU_M0805"))
    )
    (comp (ref "R3")
      (value "10k")
      (footprint "eagle-import:M0805")
      (libsource (lib "eagle-import") (part "R-EU_M0805"))
    )
    (comp (ref "R4")
      (value "0")
      (footprint "eagle-import:M0805")
      (libsource (lib "eagle-import") (part "R-EU_M0805"))
    )
    (comp (ref "R5")
      (value "0")
      (footprint "eagle-import:M0805")
      (libsource (lib "eagle-import") (part "R-EU_M0805"))
    )
    (comp (ref "R6")
      (value "330")
      (footprint "eagle-import:M0805")
      (libsource (lib "eagle-import") (part "R-EU_M0805"))
    )
    (comp (ref "R7")
      (value "4k7")
      (footprint "eagle-import:M0805")
      (libsource (lib "eagle-import") (part "R-EU_M0805"))
    )
    (comp (ref "R8")
      (value "4k7")
      (footprint "eagle-import:M0805")
      (libsource (lib "eagle-import") (part "R-EU_M0805"))
    )
    (comp (ref "SV1")
      (value "XilinxProg")
      (footprint "eagle-import:MA06-1")
      (libsource (lib "eagle-import") (part "MA06-1"))
    )
    (comp (ref "SV2")
      (value "LatticeProg")
      (footprint "eagle-import:MA05-2")
      (libsource (lib "eagle-import") (part "MA05-2"))
    )
  )
  (nets
    (net (code "1") (name "+5V") (class "Default")
      (node (ref "C28") (pin "1") (pinfunction "1_1") (pintype "passive"))
      (node (ref "C30") (pin "+") (pinfunction "+_+") (pintype "passive"))
      (node (ref "C33") (pin "1") (pinfunction "1_1") (pintype "passive"))
      (node (ref "C35") (pin "1") (pinfunction "1_1") (pintype "passive"))
      (node (ref "C56") (pin "2") (pinfunction "2_2") (pintype "passive"))
      (node (ref "C57") (pin "2") (pinfunction "2_2") (pintype "passive"))
      (node (ref "IC10") (pin "3") (pinfunction "IN_3") (pintype "power_in"))
      (node (ref "IC6") (pin "15") (pinfunction "VCC_15") (pintype "power_in"))
      (node (ref "IC6") (pin "35") (pinfunction "VCC_35") (pintype "power_in"))
      (node (ref "J1") (pin "A1") (pinfunction "A1_A1") (pintype "passive"))
      (node (ref "J1") (pin "B1") (pinfunction "B1_B1") (pintype "passive"))
      (node (ref "J1") (pin "C1") (pinfunction "C1_C1") (pintype "passive"))
      (node (ref "J3") (pin "1-4") (pinfunction "4_1-4") (pintype "passive"))
      (node (ref "J3") (pin "2-4") (pinfunction "4_2-4") (pintype "passive"))
      (node (ref "R1") (pin "2") (pinfunction "2_2") (pintype "passive"))
      (node (ref "R2") (pin "2") (pinfunction "2_2") (pintype "passive"))
      (node (ref "R3") (pin "2") (pinfunction "2_2") (pintype "passive"))
      (node (ref "R37") (pin "1") (pinfunction "1_1") (pintype "passive"))
      (node (ref "R38") (pin "1") (pinfunction "1_1") (pintype "passive"))
      (node (ref "R41") (pin "1") (pinfunction "1_1") (pintype "passive"))
      (node (ref "R42") (pin "1") (pinfunction "1_1") (pintype "passive"))
    )
    (net (code "2") (name "A0") (class "Default")
      (node (ref "IC4") (pin "9") (pinfunction "A8_9") (pintype "bidirectional"))
      (node (ref "IC7") (pin "156") (pinfunction "PR2A_156") (pintype "bidirectional"))
    )
    (net (code "3") (name "A1") (class "Default")
      (node (ref "IC4") (pin "6") (pinfunction "A5_6") (pintype "bidirectional"))
      (node (ref "IC7") (pin "150") (pinfunction "PR9B_150") (pintype "bidirectional"))
    )
    (net (code "4") (name "A2") (class "Default")
      (node (ref "IC4") (pin "7") (pinfunction "A6_7") (pintype "bidirectional"))
      (node (ref "IC7") (pin "151") (pinfunction "PR9A_151") (pintype "bidirectional"))
    )
    (net (code "5") (name "A3") (class "Default")
      (node (ref "IC4") (pin "8") (pinfunction "A7_8") (pintype "bidirectional"))
      (node (ref "IC7") (pin "155") (pinfunction "PR2B_155") (pintype "bidirectional"))
    )
    (net (code "6") (name "A4") (class "Default")
      (node (ref "IC4") (pin "5") (pinfunction "A4_5") (pintype "bidirectional"))
      (node (ref "IC7") (pin "149") (pinfunction "PR10A_149") (pintype "bidirectional"))
    )
    (net (code "7") (name "A5") (class "Default")
      (node (ref "IC4") (pin "3") (pinfunction "A2_3") (pintype "bidirectional"))
      (node (ref "IC7") (pin "147") (pinfunction "PR10B_147") (pintype "bidirectional"))
    )
    (net (code "8") (name "A6") (class "Default")
      (node (ref "IC3") (pin "4") (pinfunction "A3_4") (pintype "bidirectional"))
      (node (ref "IC7") (pin "142") (pinfunction "PR13A_142") (pintype "bidirectional"))
    )
    (net (code "9") (name "A7") (class "Default")
      (node (ref "IC4") (pin "2") (pinfunction "A1_2") (pintype "bidirectional"))
      (node (ref "IC7") (pin "146") (pinfunction "PR12A_146") (pintype "bidirectional"))
    )
    (net (code "10") (name "A8") (class "Default")
      (node (ref "IC4") (pin "4") (pinfunction "A3_4") (pintype "bidirectional"))
      (node (ref "IC7") (pin "148") (pinfunction "PR11A_148") (pintype "bidirectional"))
    )
    (net (code "11") (name "A9") (class "Default")
      (node (ref "IC5") (pin "9") (pinfunction "A8_9") (pintype "bidirectional"))
      (node (ref "IC7") (pin "121") (pinfunction "PR20A_121") (pintype "bidirectional"))
    )
    (net (code "12") (name "A10") (class "Default")
      (node (ref "IC3") (pin "9") (pinfunction "A8_9") (pintype "bidirectional"))
      (node (ref "IC7") (pin "136") (pinfunction "PR15B_136") (pintype "bidirectional"))
    )
    (net (code "13") (name "A11") (class "Default")
      (node (ref "IC3") (pin "7") (pinfunction "A6_7") (pintype "bidirectional"))
      (node (ref "IC7") (pin "138") (pinfunction "PR14B_138") (pintype "bidirectional"))
    )
    (net (code "14") (name "A12") (class "Default")
      (node (ref "IC5") (pin "6") (pinfunction "A5_6") (pintype "bidirectional"))
      (node (ref "IC7") (pin "124") (pinfunction "PR19A_124") (pintype "bidirectional"))
    )
    (net (code "15") (name "A13") (class "Default")
      (node (ref "IC5") (pin "8") (pinfunction "A7_8") (pintype "bidirectional"))
      (node (ref "IC7") (pin "122") (pinfunction "PR19B_122") (pintype "bidirectional"))
    )
    (net (code "16") (name "A14") (class "Default")
      (node (ref "IC5") (pin "2") (pinfunction "A1_2") (pintype "bidirectional"))
      (node (ref "IC7") (pin "135") (pinfunction "PR16A_135") (pintype "bidirectional"))
    )
    (net (code "17") (name "A15") (class "Default")
      (node (ref "IC5") (pin "7") (pinfunction "A6_7") (pintype "bidirectional"))
      (node (ref "IC7") (pin "123") (pinfunction "PR18B_123") (pintype "bidirectional"))
    )
    (net (code "18") (name "A16") (class "Default")
      (node (ref "IC5") (pin "3") (pinfunction "A2_3") (pintype "bidirectional"))
      (node (ref "IC7") (pin "125") (pinfunction "PR18A_125") (pintype "bidirectional"))
    )
    (net (code "19") (name "A17") (class "Default")
      (node (ref "IC3") (pin "8") (pinfunction "A7_8") (pintype "bidirectional"))
      (node (ref "IC7") (pin "137") (pinfunction "PR15A_137") (pintype "bidirectional"))
    )
    (net (code "20") (name "A18") (class "Default")
      (node (ref "IC3") (pin "3") (pinfunction "A2_3") (pintype "bidirectional"))
      (node (ref "IC7") (pin "144") (pinfunction "PR12B_144") (pintype "bidirectional"))
    )
    (net (code "21") (name "A19") (class "Default")
      (node (ref "IC3") (pin "2") (pinfunction "A1_2") (pintype "bidirectional"))
      (node (ref "IC6") (pin "19") (pinfunction "2/17_19") (pintype "bidirectional"))
      (node (ref "JP3") (pin "1") (pinfunction "1_1") (pintype "passive"))
    )
    (net (code "22") (name "AUDIO_L") (class "Default")
      (node (ref "IC7") (pin "30") (pinfunction "PL18A_30") (pintype "bidirectional"))
      (node (ref "JP11") (pin "1") (pinfunction "1_1") (pintype "passive"))
      (node (ref "R40") (pin "1") (pinfunction "1_1") (pintype "passive"))
    )
    (net (code "23") (name "AUDIO_R") (class "Default")
      (node (ref "IC7") (pin "31") (pinfunction "PL19A_31") (pintype "bidirectional"))
      (node (ref "JP12") (pin "1") (pinfunction "1_1") (pintype "passive"))
      (node (ref "R39") (pin "1") (pinfunction "1_1") (pintype "passive"))
    )
    (net (code "24") (name "B_020_A0") (class "Default")
      (node (ref "IC3") (pin "15") (pinfunction "B4_15") (pintype "bidirectional"))
      (node (ref "J1") (pin "A15") (pinfunction "A15_A15") (pintype "passive"))
    )
    (net (code "25") (name "B_020_A1") (class "Default")
      (node (ref "IC3") (pin "14") (pinfunction "B5_14") (pintype "bidirectional"))
      (node (ref "J1") (pin "A16") (pinfunction "A16_A16") (pintype "passive"))
    )
    (net (code "26") (name "B_A0") (class "Default")
      (node (ref "IC4") (pin "11") (pinfunction "B8_11") (pintype "bidirectional"))
      (node (ref "J1") (pin "C5") (pinfunction "C5_C5") (pintype "passive"))
    )
    (net (code "27") (name "B_A1") (class "Default")
      (node (ref "IC4") (pin "14") (pinfunction "B5_14") (pintype "bidirectional"))
      (node (ref "J1") (pin "C7") (pinfunction "C7_C7") (pintype "passive"))
    )
    (net (code "28") (name "B_A2") (class "Default")
      (node (ref "IC4") (pin "13") (pinfunction "B6_13") (pintype "bidirectional"))
      (node (ref "J1") (pin "A6") (pinfunction "A6_A6") (pintype "passive"))
    )
    (net (code "29") (name "B_A3") (class "Default")
      (node (ref "IC4") (pin "12") (pinfunction "B7_12") (pintype "bidirectional"))
      (node (ref "J1") (pin "C6") (pinfunction "C6_C6") (pintype "passive"))
    )
    (net (code "30") (name "B_A4") (class "Default")
      (node (ref "IC4") (pin "15") (pinfunction "B4_15") (pintype "bidirectional"))
      (node (ref "J1") (pin "A7") (pinfunction "A7_A7") (pintype "passive"))
    )
    (net (code "31") (name "B_A5") (class "Default")
      (node (ref "IC4") (pin "17") (pinfunction "B2_17") (pintype "bidirectional"))
      (node (ref "J1") (pin "A8") (pinfunction "A8_A8") (pintype "passive"))
    )
    (net (code "32") (name "B_A6") (class "Default")
      (node (ref "IC3") (pin "16") (pinfunction "B3_16") (pintype "bidirectional"))
      (node (ref "J1") (pin "A9") (pinfunction "A9_A9") (pintype "passive"))
    )
    (net (code "33") (name "B_A7") (class "Default")
      (node (ref "IC4") (pin "18") (pinfunction "B1_18") (pintype "bidirectional"))
      (node (ref "J1") (pin "C9") (pinfunction "C9_C9") (pintype "passive"))
    )
    (net (code "34") (name "B_A8") (class "Default")
      (node (ref "IC4") (pin "16") (pinfunction "B3_16") (pintype "bidirectional"))
      (node (ref "J1") (pin "C8") (pinfunction "C8_C8") (pintype "passive"))
    )
    (net (code "35") (name "B_A9") (class "Default")
      (node (ref "IC5") (pin "11") (pinfunction "B8_11") (pintype "bidirectional"))
      (node (ref "J1") (pin "A30") (pinfunction "A30_A30") (pintype "passive"))
    )
    (net (code "36") (name "B_A10") (class "Default")
      (node (ref "IC3") (pin "11") (pinfunction "B8_11") (pintype "bidirectional"))
      (node (ref "J1") (pin "C18") (pinfunction "C18_C18") (pintype "passive"))
    )
    (net (code "37") (name "B_A11") (class "Default")
      (node (ref "IC3") (pin "13") (pinfunction "B6_13") (pintype "bidirectional"))
      (node (ref "J1") (pin "C17") (pinfunction "C17_C17") (pintype "passive"))
    )
    (net (code "38") (name "B_A12") (class "Default")
      (node (ref "IC5") (pin "14") (pinfunction "B5_14") (pintype "bidirectional"))
      (node (ref "J1") (pin "C27") (pinfunction "C27_C27") (pintype "passive"))
    )
    (net (code "39") (name "B_A13") (class "Default")
      (node (ref "IC5") (pin "12") (pinfunction "B7_12") (pintype "bidirectional"))
      (node (ref "J1") (pin "A29") (pinfunction "A29_A29") (pintype "passive"))
    )
    (net (code "40") (name "B_A14") (class "Default")
      (node (ref "IC5") (pin "18") (pinfunction "B1_18") (pintype "bidirectional"))
      (node (ref "J1") (pin "A18") (pinfunction "A18_A18") (pintype "passive"))
    )
    (net (code "41") (name "B_A15") (class "Default")
      (node (ref "IC5") (pin "13") (pinfunction "B6_13") (pintype "bidirectional"))
      (node (ref "J1") (pin "C28") (pinfunction "C28_C28") (pintype "passive"))
    )
    (net (code "42") (name "B_A16") (class "Default")
      (node (ref "IC5") (pin "17") (pinfunction "B2_17") (pintype "bidirectional"))
      (node (ref "J1") (pin "C19") (pinfunction "C19_C19") (pintype "passive"))
    )
    (net (code "43") (name "B_A17") (class "Default")
      (node (ref "IC3") (pin "12") (pinfunction "B7_12") (pintype "bidirectional"))
      (node (ref "J1") (pin "A17") (pinfunction "A17_A17") (pintype "passive"))
    )
    (net (code "44") (name "B_A18") (class "Default")
      (node (ref "IC3") (pin "17") (pinfunction "B2_17") (pintype "bidirectional"))
      (node (ref "J1") (pin "A12") (pinfunction "A12_A12") (pintype "passive"))
    )
    (net (code "45") (name "B_A19") (class "Default")
      (node (ref "IC3") (pin "18") (pinfunction "B1_18") (pintype "bidirectional"))
      (node (ref "J1") (pin "C12") (pinfunction "C12_C12") (pintype "passive"))
    )
    (net (code "46") (name "B_A20") (class "Default")
      (node (ref "IC6") (pin "29") (pinfunction "2/10_29") (pintype "bidirectional"))
      (node (ref "J1") (pin "B2") (pinfunction "B2_B2") (pintype "passive"))
    )
    (net (code "47") (name "B_A21") (class "Default")
      (node (ref "IC6") (pin "30") (pinfunction "2/9_30") (pintype "bidirectional"))
      (node (ref "J1") (pin "B3") (pinfunction "B3_B3") (pintype "passive"))
    )
    (net (code "48") (name "B_A22") (class "Default")
      (node (ref "IC6") (pin "31") (pinfunction "2/8_31") (pintype "bidirectional"))
      (node (ref "J1") (pin "B4") (pinfunction "B4_B4") (pintype "passive"))
    )
    (net (code "49") (name "B_A23") (class "Default")
      (node (ref "IC6") (pin "32") (pinfunction "2/7_32") (pintype "bidirectional"))
      (node (ref "J1") (pin "B5") (pinfunction "B5_B5") (pintype "passive"))
    )
    (net (code "50") (name "B_A24") (class "Default")
      (node (ref "IC6") (pin "33") (pinfunction "2/6_33") (pintype "bidirectional"))
      (node (ref "J1") (pin "C10") (pinfunction "C10_C10") (pintype "passive"))
    )
    (net (code "51") (name "B_A25") (class "Default")
      (node (ref "IC6") (pin "36") (pinfunction "2/3_36") (pintype "bidirectional"))
      (node (ref "J1") (pin "C11") (pinfunction "C11_C11") (pintype "passive"))
    )
    (net (code "52") (name "B_A26") (class "Default")
      (node (ref "IC6") (pin "39") (pinfunction "2/1_39") (pintype "bidirectional"))
      (node (ref "J1") (pin "A14") (pinfunction "A14_A14") (pintype "passive"))
    )
    (net (code "53") (name "B_A27") (class "Default")
      (node (ref "IC6") (pin "40") (pinfunction "1/1_40") (pintype "bidirectional"))
      (node (ref "J1") (pin "C15") (pinfunction "C15_C15") (pintype "passive"))
    )
    (net (code "54") (name "B_A28") (class "Default")
      (node (ref "IC6") (pin "41") (pinfunction "1/2_41") (pintype "bidirectional"))
      (node (ref "J1") (pin "C16") (pinfunction "C16_C16") (pintype "passive"))
    )
    (net (code "55") (name "B_A29") (class "Default")
      (node (ref "IC6") (pin "42") (pinfunction "1/4_42") (pintype "bidirectional"))
      (node (ref "J1") (pin "A19") (pinfunction "A19_A19") (pintype "passive"))
    )
    (net (code "56") (name "B_D0") (class "Default")
      (node (ref "IC1") (pin "17") (pinfunction "B2_17") (pintype "bidirectional"))
      (node (ref "J1") (pin "C2") (pinfunction "C2_C2") (pintype "passive"))
    )
    (net (code "57") (name "B_D1") (class "Default")
      (node (ref "IC2") (pin "11") (pinfunction "B8_11") (pintype "bidirectional"))
      (node (ref "J1") (pin "C14") (pinfunction "C14_C14") (pintype "passive"))
    )
    (net (code "58") (name "B_D2") (class "Default")
      (node (ref "IC1") (pin "13") (pinfunction "B6_13") (pintype "bidirectional"))
      (node (ref "J1") (pin "C4") (pinfunction "C4_C4") (pintype "passive"))
    )
    (net (code "59") (name "B_D3") (class "Default")
      (node (ref "IC1") (pin "14") (pinfunction "B5_14") (pintype "bidirectional"))
      (node (ref "J1") (pin "A4") (pinfunction "A4_A4") (pintype "passive"))
    )
    (net (code "60") (name "B_D4") (class "Default")
      (node (ref "IC1") (pin "12") (pinfunction "B7_12") (pintype "bidirectional"))
      (node (ref "J1") (pin "A5") (pinfunction "A5_A5") (pintype "passive"))
    )
    (net (code "61") (name "B_D5") (class "Default")
      (node (ref "IC1") (pin "18") (pinfunction "B1_18") (pintype "bidirectional"))
      (node (ref "J1") (pin "A2") (pinfunction "A2_A2") (pintype "passive"))
    )
    (net (code "62") (name "B_D6") (class "Default")
      (node (ref "IC1") (pin "16") (pinfunction "B3_16") (pintype "bidirectional"))
      (node (ref "J1") (pin "A3") (pinfunction "A3_A3") (pintype "passive"))
    )
    (net (code "63") (name "B_D7") (class "Default")
      (node (ref "IC1") (pin "15") (pinfunction "B4_15") (pintype "bidirectional"))
      (node (ref "J1") (pin "C3") (pinfunction "C3_C3") (pintype "passive"))
    )
    (net (code "64") (name "B_D8") (class "Default")
      (node (ref "IC1") (pin "11") (pinfunction "B8_11") (pintype "bidirectional"))
      (node (ref "J1") (pin "B6") (pinfunction "B6_B6") (pintype "passive"))
    )
    (net (code "65") (name "B_D9") (class "Default")
      (node (ref "IC2") (pin "18") (pinfunction "B1_18") (pintype "bidirectional"))
      (node (ref "J1") (pin "B7") (pinfunction "B7_B7") (pintype "passive"))
    )
    (net (code "66") (name "B_D10") (class "Default")
      (node (ref "IC2") (pin "17") (pinfunction "B2_17") (pintype "bidirectional"))
      (node (ref "J1") (pin "B8") (pinfunction "B8_B8") (pintype "passive"))
    )
    (net (code "67") (name "B_D11") (class "Default")
      (node (ref "IC2") (pin "16") (pinfunction "B3_16") (pintype "bidirectional"))
      (node (ref "J1") (pin "B9") (pinfunction "B9_B9") (pintype "passive"))
    )
    (net (code "68") (name "B_D12") (class "Default")
      (node (ref "IC2") (pin "15") (pinfunction "B4_15") (pintype "bidirectional"))
      (node (ref "J1") (pin "B10") (pinfunction "B10_B10") (pintype "passive"))
    )
    (net (code "69") (name "B_D13") (class "Default")
      (node (ref "IC2") (pin "14") (pinfunction "B5_14") (pintype "bidirectional"))
      (node (ref "J1") (pin "B11") (pinfunction "B11_B11") (pintype "passive"))
    )
    (net (code "70") (name "B_D14") (class "Default")
      (node (ref "IC2") (pin "13") (pinfunction "B6_13") (pintype "bidirectional"))
      (node (ref "J1") (pin "B12") (pinfunction "B12_B12") (pintype "passive"))
    )
    (net (code "71") (name "B_D15") (class "Default")
      (node (ref "IC2") (pin "12") (pinfunction "B7_12") (pintype "bidirectional"))
      (node (ref "J1") (pin "B13") (pinfunction "B13_B13") (pintype "passive"))
    )
    (net (code "72") (name "B_D16") (class "Default")
      (node (ref "J1") (pin "B22") (pinfunction "B22_B22") (pintype "passive"))
    )
    (net (code "73") (name "B_D17") (class "Default")
      (node (ref "J1") (pin "B23") (pinfunction "B23_B23") (pintype "passive"))
    )
    (net (code "74") (name "B_D18") (class "Default")
      (node (ref "J1") (pin "B24") (pinfunction "B24_B24") (pintype "passive"))
    )
    (net (code "75") (name "B_D19") (class "Default")
      (node (ref "J1") (pin "B25") (pinfunction "B25_B25") (pintype "passive"))
    )
    (net (code "76") (name "B_D20") (class "Default")
      (node (ref "J1") (pin "B26") (pinfunction "B26_B26") (pintype "passive"))
    )
    (net (code "77") (name "B_D21") (class "Default")
      (node (ref "J1") (pin "B27") (pinfunction "B27_B27") (pintype "passive"))
    )
    (net (code "78") (name "B_D22") (class "Default")
      (node (ref "J1") (pin "B30") (pinfunction "B30_B30") (pintype "passive"))
    )
    (net (code "79") (name "B_D23") (class "Default")
      (node (ref "J1") (pin "B31") (pinfunction "B31_B31") (pintype "passive"))
    )
    (net (code "80") (name "B_D24") (class "Default")
      (node (ref "J1") (pin "B14") (pinfunction "B14_B14") (pintype "passive"))
    )
    (net (code "81") (name "B_D25") (class "Default")
      (node (ref "J1") (pin "B15") (pinfunction "B15_B15") (pintype "passive"))
    )
    (net (code "82") (name "B_D26") (class "Default")
      (node (ref "J1") (pin "B16") (pinfunction "B16_B16") (pintype "passive"))
    )
    (net (code "83") (name "B_D27") (class "Default")
      (node (ref "J1") (pin "A22") (pinfunction "A22_A22") (pintype "passive"))
    )
    (net (code "84") (name "B_D28") (class "Default")
      (node (ref "J1") (pin "A23") (pinfunction "A23_A23") (pintype "passive"))
    )
    (net (code "85") (name "B_D29") (class "Default")
      (node (ref "J1") (pin "A24") (pinfunction "A24_A24") (pintype "passive"))
    )
    (net (code "86") (name "B_D30") (class "Default")
      (node (ref "J1") (pin "A25") (pinfunction "A25_A25") (pintype "passive"))
    )
    (net (code "87") (name "B_D31") (class "Default")
      (node (ref "J1") (pin "A26") (pinfunction "A26_A26") (pintype "passive"))
    )
    (net (code "88") (name "B_IOR") (class "Default")
      (node (ref "IC6") (pin "3") (pinfunction "1/8_3") (pintype "bidirectional"))
      (node (ref "J1") (pin "A27") (pinfunction "A27_A27") (pintype "passive"))
    )
    (net (code "89") (name "B_MEMR") (class "Default")
      (node (ref "IC6") (pin "7") (pinfunction "1/11_7") (pintype "bidirectional"))
      (node (ref "J1") (pin "C30") (pinfunction "C30_C30") (pintype "passive"))
    )
    (net (code "90") (name "B_RD") (class "Default")
      (node (ref "IC5") (pin "15") (pinfunction "B4_15") (pintype "bidirectional"))
      (node (ref "J1") (pin "C24") (pinfunction "C24_C24") (pintype "passive"))
    )
    (net (code "91") (name "B_RESET") (class "Default")
      (node (ref "IC6") (pin "8") (pinfunction "1/12_8") (pintype "bidirectional"))
      (node (ref "J1") (pin "C31") (pinfunction "C31_C31") (pintype "passive"))
    )
    (net (code "92") (name "B_WR") (class "Default")
      (node (ref "IC5") (pin "16") (pinfunction "B3_16") (pintype "bidirectional"))
      (node (ref "J1") (pin "C22") (pinfunction "C22_C22") (pintype "passive"))
    )
    (net (code "93") (name "CLK") (class "Default")
      (node (ref "IC7") (pin "32") (pinfunction "PL18B_32") (pintype "bidirectional"))
      (node (ref "R6") (pin "1") (pinfunction "1_1") (pintype "passive"))
    )
    (net (code "94") (name "D0") (class "Default")
      (node (ref "IC1") (pin "3") (pinfunction "A2_3") (pintype "bidirectional"))
      (node (ref "IC7") (pin "178") (pinfunction "PT21A_178") (pintype "bidirectional"))
    )
    (net (code "95") (name "D1") (class "Default")
      (node (ref "IC2") (pin "9") (pinfunction "A8_9") (pintype "bidirectional"))
      (node (ref "IC7") (pin "157") (pinfunction "PT32B_157") (pintype "bidirectional"))
    )
    (net (code "96") (name "D2") (class "Default")
      (node (ref "IC1") (pin "7") (pinfunction "A6_7") (pintype "bidirectional"))
      (node (ref "IC7") (pin "174") (pinfunction "PT22B_174") (pintype "bidirectional"))
    )
    (net (code "97") (name "D3") (class "Default")
      (node (ref "IC1") (pin "6") (pinfunction "A5_6") (pintype "bidirectional"))
      (node (ref "IC7") (pin "175") (pinfunction "PT23A_175") (pintype "bidirectional"))
    )
    (net (code "98") (name "D4") (class "Default")
      (node (ref "IC1") (pin "8") (pinfunction "A7_8") (pintype "bidirectional"))
      (node (ref "IC7") (pin "173") (pinfunction "PT23B_173") (pintype "bidirectional"))
    )
    (net (code "99") (name "D5") (class "Default")
      (node (ref "IC1") (pin "2") (pinfunction "A1_2") (pintype "bidirectional"))
      (node (ref "IC7") (pin "179") (pinfunction "PT20B_179") (pintype "bidirectional"))
    )
    (net (code "100") (name "D6") (class "Default")
      (node (ref "IC1") (pin "4") (pinfunction "A3_4") (pintype "bidirectional"))
      (node (ref "IC7") (pin "177") (pinfunction "PT21B_177") (pintype "bidirectional"))
    )
    (net (code "101") (name "D7") (class "Default")
      (node (ref "IC1") (pin "5") (pinfunction "A4_5") (pintype "bidirectional"))
      (node (ref "IC7") (pin "176") (pinfunction "PT22A_176") (pintype "bidirectional"))
    )
    (net (code "102") (name "D8") (class "Default")
      (node (ref "IC1") (pin "9") (pinfunction "A8_9") (pintype "bidirectional"))
      (node (ref "IC7") (pin "170") (pinfunction "PT24A_170") (pintype "bidirectional"))
    )
    (net (code "103") (name "D9") (class "Default")
      (node (ref "IC2") (pin "2") (pinfunction "A1_2") (pintype "bidirectional"))
      (node (ref "IC7") (pin "168") (pinfunction "PT24B_168") (pintype "bidirectional"))
    )
    (net (code "104") (name "D10") (class "Default")
      (node (ref "IC2") (pin "3") (pinfunction "A2_3") (pintype "bidirectional"))
      (node (ref "IC7") (pin "167") (pinfunction "PT25B_167") (pintype "bidirectional"))
    )
    (net (code "105") (name "D11") (class "Default")
      (node (ref "IC2") (pin "4") (pinfunction "A3_4") (pintype "bidirectional"))
      (node (ref "IC7") (pin "164") (pinfunction "PT30A_164") (pintype "bidirectional"))
    )
    (net (code "106") (name "D12") (class "Default")
      (node (ref "IC2") (pin "5") (pinfunction "A4_5") (pintype "bidirectional"))
      (node (ref "IC7") (pin "163") (pinfunction "PT30B_163") (pintype "bidirectional"))
    )
    (net (code "107") (name "D13") (class "Default")
      (node (ref "IC2") (pin "6") (pinfunction "A5_6") (pintype "bidirectional"))
      (node (ref "IC7") (pin "160") (pinfunction "PT31A_160") (pintype "bidirectional"))
    )
    (net (code "108") (name "D14") (class "Default")
      (node (ref "IC2") (pin "7") (pinfunction "A6_7") (pintype "bidirectional"))
      (node (ref "IC7") (pin "159") (pinfunction "PT32A_159") (pintype "bidirectional"))
    )
    (net (code "109") (name "D15") (class "Default")
      (node (ref "IC2") (pin "8") (pinfunction "A7_8") (pintype "bidirectional"))
      (node (ref "IC7") (pin "158") (pinfunction "PT31B_158") (pintype "bidirectional"))
    )
    (net (code "110") (name "DIR") (class "Default")
      (node (ref "IC1") (pin "1") (pinfunction "DIR_1") (pintype "input"))
      (node (ref "IC2") (pin "1") (pinfunction "DIR_1") (pintype "input"))
      (node (ref "IC7") (pin "169") (pinfunction "PT25A_169") (pintype "bidirectional"))
    )
    (net (code "111") (name "DMACK") (class "Default")
      (node (ref "CON1") (pin "44") (pinfunction "/REG_44") (pintype "input"))
      (node (ref "JP15") (pin "1") (pinfunction "1_1") (pintype "passive"))
      (node (ref "R16") (pin "1") (pinfunction "1_1") (pintype "passive"))
      (node (ref "X1") (pin "29") (pinfunction "S_29") (pintype "passive"))
    )
    (net (code "112") (name "ETH_CS") (class "Default")
      (node (ref "IC12") (pin "9") (pinfunction "~{CS}_9") (pintype "input"))
      (node (ref "IC7") (pin "20") (pinfunction "PL15A_20") (pintype "bidirectional"))
      (node (ref "JP8") (pin "1") (pinfunction "1_1") (pintype "passive"))
    )
    (net (code "113") (name "ETH_INT") (class "Default")
      (node (ref "IC12") (pin "4") (pinfunction "~{INT}_4") (pintype "output"))
      (node (ref "IC7") (pin "21") (pinfunction "PL15B_21") (pintype "bidirectional"))
      (node (ref "JP9") (pin "1") (pinfunction "1_1") (pintype "passive"))
    )
    (net (code "114") (name "F_020_A0") (class "Default")
      (node (ref "IC3") (pin "5") (pinfunction "A4_5") (pintype "bidirectional"))
      (node (ref "IC7") (pin "140") (pinfunction "PR14A_140") (pintype "bidirectional"))
    )
    (net (code "115") (name "F_020_A1") (class "Default")
      (node (ref "IC3") (pin "6") (pinfunction "A5_6") (pintype "bidirectional"))
      (node (ref "IC7") (pin "139") (pinfunction "PR13B_139") (pintype "bidirectional"))
    )
    (net (code "116") (name "F_INT") (class "Default")
      (node (ref "IC6") (pin "22") (pinfunction "2/14_22") (pintype "bidirectional"))
      (node (ref "IC7") (pin "116") (pinfunction "PR21B_116") (pintype "bidirectional"))
    )
    (net (code "117") (name "F_IORQ") (class "Default")
      (node (ref "IC6") (pin "16") (pinfunction "1/16_16") (pintype "bidirectional"))
      (node (ref "IC7") (pin "112") (pinfunction "PR22B_112") (pintype "bidirectional"))
    )
    (net (code "118") (name "F_IRQ0") (class "Default")
      (node (ref "IC6") (pin "21") (pinfunction "2/15_21") (pintype "bidirectional"))
      (node (ref "IC7") (pin "115") (pinfunction "PR23A_115") (pintype "bidirectional"))
    )
    (net (code "119") (name "F_IRQ1") (class "Default")
      (node (ref "IC6") (pin "20") (pinfunction "2/16_20") (pintype "bidirectional"))
      (node (ref "IC7") (pin "114") (pinfunction "PR22A_114") (pintype "bidirectional"))
    )
    (net (code "120") (name "F_LDS_SIZ1") (class "Default")
      (node (ref "IC6") (pin "14") (pinfunction "1/15_14") (pintype "bidirectional"))
      (node (ref "IC7") (pin "111") (pinfunction "PR24B_111") (pintype "bidirectional"))
    )
    (net (code "121") (name "F_MEMRQ") (class "Default")
      (node (ref "IC6") (pin "13") (pinfunction "1/14_13") (pintype "bidirectional"))
      (node (ref "IC7") (pin "110") (pinfunction "PR24A_110") (pintype "bidirectional"))
    )
    (net (code "122") (name "F_NMI") (class "Default")
      (node (ref "IC6") (pin "23") (pinfunction "2/13_23") (pintype "bidirectional"))
      (node (ref "IC7") (pin "118") (pinfunction "PR21A_118") (pintype "bidirectional"))
    )
    (net (code "123") (name "F_RD") (class "Default")
      (node (ref "IC5") (pin "5") (pinfunction "A4_5") (pintype "bidirectional"))
      (node (ref "IC7") (pin "105") (pinfunction "PR30A_105") (pintype "bidirectional"))
    )
    (net (code "124") (name "F_RESET") (class "Default")
      (node (ref "IC6") (pin "28") (pinfunction "2/11_28") (pintype "bidirectional"))
      (node (ref "IC7") (pin "8") (pinfunction "PL10A_8") (pintype "bidirectional"))
      (node (ref "JP16") (pin "1") (pinfunction "1_1") (pintype "passive"))
      (node (ref "JP30") (pin "1") (pinfunction "1_1") (pintype "passive"))
      (node (ref "R19") (pin "2") (pinfunction "2_2") (pintype "passive"))
      (node (ref "R43") (pin "2") (pinfunction "2_2") (pintype "passive"))
    )
    (net (code "125") (name "F_TCK") (class "Default")
      (node (ref "IC7") (pin "127") (pinfunction "TCK_127") (pintype "input"))
      (node (ref "R8") (pin "2") (pinfunction "2_2") (pintype "passive"))
      (node (ref "SV2") (pin "1") (pinfunction "1_1") (pintype "passive"))
    )
    (net (code "126") (name "F_TDI") (class "Default")
      (node (ref "IC7") (pin "128") (pinfunction "TDI_128") (pintype "input"))
      (node (ref "SV2") (pin "5") (pinfunction "5_5") (pintype "passive"))
    )
    (net (code "127") (name "F_TDO") (class "Default")
      (node (ref "IC7") (pin "129") (pinfunction "TDO_129") (pintype "output"))
      (node (ref "SV2") (pin "7") (pinfunction "7_7") (pintype "passive"))
    )
    (net (code "128") (name "F_TMS") (class "Default")
      (node (ref "IC7") (pin "126") (pinfunction "TMS_126") (pintype "input"))
      (node (ref "SV2") (pin "3") (pinfunction "3_3") (pintype "passive"))
    )
    (net (code "129") (name "F_UDS_SIZ0") (class "Default")
      (node (ref "IC6") (pin "18") (pinfunction "1/17_18") (pintype "bidirectional"))
      (node (ref "IC7") (pin "113") (pinfunction "PR23B_113") (pintype "bidirectional"))
    )
    (net (code "130") (name "F_WAIT") (class "Default")
      (node (ref "IC6") (pin "27") (pinfunction "2/12_27") (pintype "bidirectional"))
      (node (ref "IC7") (pin "120") (pinfunction "PR20B_120") (pintype "bidirectional"))
    )
    (net (code "131") (name "F_WR") (class "Default")
      (node (ref "IC5") (pin "4") (pinfunction "A3_4") (pintype "bidirectional"))
      (node (ref "IC7") (pin "106") (pinfunction "PR30B_106") (pintype "bidirectional"))
    )
    (net (code "132") (name "GND") (class "Default")
      (node (ref "C1") (pin "2") (pinfunction "2_2") (pintype "passive"))
      (node (ref "C10") (pin "2") (pinfunction "2_2") (pintype "passive"))
      (node (ref "C11") (pin "-") (pinfunction "-_-") (pintype "passive"))
      (node (ref "C12") (pin "-") (pinfunction "-_-") (pintype "passive"))
      (node (ref "C13") (pin "2") (pinfunction "2_2") (pintype "passive"))
      (node (ref "C14") (pin "2") (pinfunction "2_2") (pintype "passive"))
      (node (ref "C15") (pin "-") (pinfunction "-_-") (pintype "passive"))
      (node (ref "C16") (pin "2") (pinfunction "2_2") (pintype "passive"))
      (node (ref "C17") (pin "2") (pinfunction "2_2") (pintype "passive"))
      (node (ref "C18") (pin "-") (pinfunction "-_-") (pintype "passive"))
      (node (ref "C19") (pin "-") (pinfunction "-_-") (pintype "passive"))
      (node (ref "C2") (pin "2") (pinfunction "2_2") (pintype "passive"))
      (node (ref "C20") (pin "-") (pinfunction "-_-") (pintype "passive"))
      (node (ref "C21") (pin "2") (pinfunction "2_2") (pintype "passive"))
      (node (ref "C22") (pin "-") (pinfunction "-_-") (pintype "passive"))
      (node (ref "C23") (pin "2") (pinfunction "2_2") (pintype "passive"))
      (node (ref "C24") (pin "-") (pinfunction "-_-") (pintype "passive"))
      (node (ref "C25") (pin "2") (pinfunction "2_2") (pintype "passive"))
      (node (ref "C26") (pin "2") (pinfunction "2_2") (pintype "passive"))
      (node (ref "C27") (pin "2") (pinfunction "2_2") (pintype "passive"))
      (node (ref "C28") (pin "2") (pinfunction "2_2") (pintype "passive"))
      (node (ref "C29") (pin "2") (pinfunction "2_2") (pintype "passive"))
      (node (ref "C3") (pin "2") (pinfunction "2_2") (pintype "passive"))
      (node (ref "C30") (pin "-") (pinfunction "-_-") (pintype "passive"))
      (node (ref "C31") (pin "2") (pinfunction "2_2") (pintype "passive"))
      (node (ref "C32") (pin "2") (pinfunction "2_2") (pintype "passive"))
      (node (ref "C33") (pin "2") (pinfunction "2_2") (pintype "passive"))
      (node (ref "C34") (pin "2") (pinfunction "2_2") (pintype "passive"))
      (node (ref "C35") (pin "2") (pinfunction "2_2") (pintype "passive"))
      (node (ref "C36") (pin "2") (pinfunction "2_2") (pintype "passive"))
      (node (ref "C37") (pin "2") (pinfunction "2_2") (pintype "passive"))
      (node (ref "C38") (pin "2") (pinfunction "2_2") (pintype "passive"))
      (node (ref "C39") (pin "2") (pinfunction "2_2") (pintype "passive"))
      (node (ref "C4") (pin "-") (pinfunction "-_-") (pintype "passive"))
      (node (ref "C40") (pin "2") (pinfunction "2_2") (pintype "passive"))
      (node (ref "C41") (pin "2") (pinfunction "2_2") (pintype "passive"))
      (node (ref "C42") (pin "2") (pinfunction "2_2") (pintype "passive"))
      (node (ref "C43") (pin "2") (pinfunction "2_2") (pintype "passive"))
      (node (ref "C44") (pin "2") (pinfunction "2_2") (pintype "passive"))
      (node (ref "C45") (pin "2") (pinfunction "2_2") (pintype "passive"))
      (node (ref "C46") (pin "2") (pinfunction "2_2") (pintype "passive"))
      (node (ref "C47") (pin "2") (pinfunction "2_2") (pintype "passive"))
      (node (ref "C48") (pin "2") (pinfunction "2_2") (pintype "passive"))
      (node (ref "C5") (pin "2") (pinfunction "2_2") (pintype "passive"))
      (node (ref "C52") (pin "2") (pinfunction "2_2") (pintype "passive"))
      (node (ref "C53") (pin "2") (pinfunction "2_2") (pintype "passive"))
      (node (ref "C54") (pin "2") (pinfunction "2_2") (pintype "passive"))
      (node (ref "C55") (pin "2") (pinfunction "2_2") (pintype "passive"))
      (node (ref "C56") (pin "1") (pinfunction "1_1") (pintype "passive"))
      (node (ref "C57") (pin "1") (pinfunction "1_1") (pintype "passive"))
      (node (ref "C58") (pin "1") (pinfunction "1_1") (pintype "passive"))
      (node (ref "C59") (pin "-") (pinfunction "-_-") (pintype "passive"))
      (node (ref "C6") (pin "2") (pinfunction "2_2") (pintype "passive"))
      (node (ref "C60") (pin "1") (pinfunction "1_1") (pintype "passive"))
      (node (ref "C61") (pin "1") (pinfunction "1_1") (pintype "passive"))
      (node (ref "C62") (pin "1") (pinfunction "1_1") (pintype "passive"))
      (node (ref "C63") (pin "1") (pinfunction "1_1") (pintype "passive"))
      (node (ref "C64") (pin "1") (pinfunction "1_1") (pintype "passive"))
      (node (ref "C65") (pin "1") (pinfunction "1_1") (pintype "passive"))
      (node (ref "C66") (pin "1") (pinfunction "1_1") (pintype "passive"))
      (node (ref "C67") (pin "1") (pinfunction "1_1") (pintype "passive"))
      (node (ref "C7") (pin "-") (pinfunction "-_-") (pintype "passive"))
      (node (ref "C8") (pin "2") (pinfunction "2_2") (pintype "passive"))
      (node (ref "C9") (pin "-") (pinfunction "-_-") (pintype "passive"))
      (node (ref "CON1") (pin "1") (pinfunction "GND1_1") (pintype "power_in"))
      (node (ref "CON1") (pin "10") (pinfunction "A09_10") (pintype "input"))
      (node (ref "CON1") (pin "11") (pinfunction "A08_11") (pintype "input"))
      (node (ref "CON1") (pin "12") (pinfunction "A07_12") (pintype "input"))
      (node (ref "CON1") (pin "14") (pinfunction "A06_14") (pintype "input"))
      (node (ref "CON1") (pin "15") (pinfunction "A05_15") (pintype "input"))
      (node (ref "CON1") (pin "16") (pinfunction "A04_16") (pintype "input"))
      (node (ref "CON1") (pin "17") (pinfunction "A03_17") (pintype "input"))
      (node (ref "CON1") (pin "50") (pinfunction "GND2_50") (pintype "power_in"))
      (node (ref "CON1") (pin "8") (pinfunction "A10_8") (pintype "input"))
      (node (ref "D1") (pin "1") (pinfunction "A_1") (pintype "passive"))
      (node (ref "D2") (pin "1") (pinfunction "A_1") (pintype "passive"))
      (node (ref "D3") (pin "1") (pinfunction "A_1") (pintype "passive"))
      (node (ref "D4") (pin "1") (pinfunction "A_1") (pintype "passive"))
      (node (ref "IC10") (pin "1") (pinfunction "ADJ_1") (pintype "power_in"))
      (node (ref "IC11") (pin "15") (pinfunction "GND_15") (pintype "power_in"))
      (node (ref "IC12") (pin "11") (pinfunction "VSSRX_11") (pintype "input"))
      (node (ref "IC12") (pin "18") (pinfunction "VSSTX_18") (pintype "input"))
      (node (ref "IC12") (pin "2") (pinfunction "VSS_2") (pintype "input"))
      (node (ref "IC12") (pin "21") (pinfunction "VSSPLL_21") (pintype "input"))
      (node (ref "IC12") (pin "22") (pinfunction "VSSOSC_22") (pintype "input"))
      (node (ref "IC13") (pin "2") (pinfunction "GND_2") (pintype "power_in"))
      (node (ref "IC3") (pin "19") (pinfunction "G_19") (pintype "input"))
      (node (ref "IC4") (pin "19") (pinfunction "G_19") (pintype "input"))
      (node (ref "IC5") (pin "19") (pinfunction "G_19") (pintype "input"))
      (node (ref "IC6") (pin "17") (pinfunction "GND_17") (pintype "power_in"))
      (node (ref "IC6") (pin "25") (pinfunction "GND_25") (pintype "power_in"))
      (node (ref "IC6") (pin "4") (pinfunction "GND_4") (pintype "power_in"))
      (node (ref "IC7") (pin "100") (pinfunction "LRC_GNDPLL_100") (pintype "power_in"))
      (node (ref "IC7") (pin "109") (pinfunction "GND_109") (pintype "power_in"))
      (node (ref "IC7") (pin "119") (pinfunction "GNDIO3_119") (pintype "power_in"))
      (node (ref "IC7") (pin "133") (pinfunction "GND_133") (pintype "power_in"))
      (node (ref "IC7") (pin "14") (pinfunction "GNDIO7_14") (pintype "power_in"))
      (node (ref "IC7") (pin "143") (pinfunction "GNDIO2_143") (pintype "power_in"))
      (node (ref "IC7") (pin "154") (pinfunction "GNDIO2_154") (pintype "power_in"))
      (node (ref "IC7") (pin "161") (pinfunction "GNDIO1_161") (pintype "power_in"))
      (node (ref "IC7") (pin "165") (pinfunction "GNDIO1_165") (pintype "power_in"))
      (node (ref "IC7") (pin "171") (pinfunction "GNDIO1_171") (pintype "power_in"))
      (node (ref "IC7") (pin "190") (pinfunction "GNDIO0_190") (pintype "power_in"))
      (node (ref "IC7") (pin "199") (pinfunction "GNDIO0_199") (pintype "power_in"))
      (node (ref "IC7") (pin "203") (pinfunction "ULC_GNDPLL_203") (pintype "power_in"))
      (node (ref "IC7") (pin "24") (pinfunction "GND_24") (pintype "power_in"))
      (node (ref "IC7") (pin "3") (pinfunction "GNDIO7_3") (pintype "power_in"))
      (node (ref "IC7") (pin "37") (pinfunction "GNDIO6_37") (pintype "power_in"))
      (node (ref "IC7") (pin "48") (pinfunction "GNDIO6_48") (pintype "power_in"))
      (node (ref "IC7") (pin "58") (pinfunction "GND_58") (pintype "power_in"))
      (node (ref "IC7") (pin "62") (pinfunction "GNDIO5_62") (pintype "power_in"))
      (node (ref "IC7") (pin "71") (pinfunction "GNDIO5_71") (pintype "power_in"))
      (node (ref "IC7") (pin "90") (pinfunction "GNDIO4_90") (pintype "power_in"))
      (node (ref "IC7") (pin "96") (pinfunction "GNDIO4_96") (pintype "power_in"))
      (node (ref "IC8") (pin "12") (pinfunction "GND_12") (pintype "power_in"))
      (node (ref "IC8") (pin "34") (pinfunction "GND_34") (pintype "power_in"))
      (node (ref "IC9") (pin "12") (pinfunction "GND_12") (pintype "power_in"))
      (node (ref "IC9") (pin "34") (pinfunction "GND_34") (pintype "power_in"))
      (node (ref "J1") (pin "A32") (pinfunction "A32_A32") (pintype "passive"))
      (node (ref "J1") (pin "B32") (pinfunction "B32_B32") (pintype "passive"))
      (node (ref "J1") (pin "C32") (pinfunction "C32_C32") (pintype "passive"))
      (node (ref "J2") (pin "3") (pinfunction "3_3") (pintype "input"))
      (node (ref "J2") (pin "6") (pinfunction "6_6") (pintype "input"))
      (node (ref "J2") (pin "S1") (pinfunction "SHIELD_S1") (pintype "passive"))
      (node (ref "J3") (pin "1-3") (pinfunction "3_1-3") (pintype "passive"))
      (node (ref "J3") (pin "10") (pinfunction "10_10") (pintype "passive"))
      (node (ref "J3") (pin "11") (pinfunction "11_11") (pintype "passive"))
      (node (ref "J3") (pin "12") (pinfunction "12_12") (pintype "passive"))
      (node (ref "J3") (pin "2-3") (pinfunction "3_2-3") (pintype "passive"))
      (node (ref "J3") (pin "6") (pinfunction "6_6") (pintype "passive"))
      (node (ref "J3") (pin "7") (pinfunction "7_7") (pintype "passive"))
      (node (ref "J3") (pin "8") (pinfunction "8_8") (pintype "passive"))
      (node (ref "J3") (pin "S1") (pinfunction "SHIELD_S1") (pintype "passive"))
      (node (ref "J3") (pin "S2") (pinfunction "SHIELD_S2") (pintype "passive"))
      (node (ref "J3") (pin "S3") (pinfunction "SHIELD_S3") (pintype "passive"))
      (node (ref "J3") (pin "S4") (pinfunction "SHIELD_S4") (pintype "passive"))
      (node (ref "J3") (pin "S5") (pinfunction "SHIELD_S5") (pintype "passive"))
      (node (ref "J3") (pin "S6") (pinfunction "SHIELD_S6") (pintype "passive"))
      (node (ref "J4") (pin "S1") (pinfunction "S1_S1") (pintype "passive"))
      (node (ref "J4") (pin "S2") (pinfunction "S2_S2") (pintype "passive"))
      (node (ref "JP1") (pin "1") (pinfunction "1_1") (pintype "passive"))
      (node (ref "JP18") (pin "5") (pinfunction "5_5") (pintype "passive"))
      (node (ref "LED1") (pin "C") (pinfunction "C_C") (pintype "passive"))
      (node (ref "QG1") (pin "4") (pinfunction "GND_4") (pintype "power_in"))
      (node (ref "R17") (pin "2") (pinfunction "2_2") (pintype "passive"))
      (node (ref "R18") (pin "2") (pinfunction "2_2") (pintype "passive"))
      (node (ref "R4") (pin "1") (pinfunction "1_1") (pintype "passive"))
      (node (ref "R44") (pin "1") (pinfunction "1_1") (pintype "passive"))
      (node (ref "R49") (pin "2") (pinfunction "2_2") (pintype "passive"))
      (node (ref "R5") (pin "1") (pinfunction "1_1") (pintype "passive"))
      (node (ref "R50") (pin "2") (pinfunction "2_2") (pintype "passive"))
      (node (ref "R8") (pin "1") (pinfunction "1_1") (pintype "passive"))
      (node (ref "SV1") (pin "2") (pinfunction "2_2") (pintype "passive"))
      (node (ref "SV2") (pin "2") (pinfunction "2_2") (pintype "passive"))
      (node (ref "SV2") (pin "4") (pinfunction "4_4") (pintype "passive"))
      (node (ref "SV2") (pin "8") (pinfunction "8_8") (pintype "passive"))
      (node (ref "X1") (pin "19") (pinfunction "S_19") (pintype "passive"))
      (node (ref "X1") (pin "2") (pinfunction "S_2") (pintype "passive"))
      (node (ref "X1") (pin "22") (pinfunction "S_22") (pintype "passive"))
      (node (ref "X1") (pin "24") (pinfunction "S_24") (pintype "passive"))
      (node (ref "X1") (pin "26") (pinfunction "S_26") (pintype "passive"))
      (node (ref "X1") (pin "32") (pinfunction "S_32") (pintype "passive"))
      (node (ref "X1") (pin "40") (pinfunction "S_40") (pintype "passive"))
      (node (ref "X2") (pin "1") (pinfunction "1_1") (pintype "passive"))
    )
    (net (code "133") (name "IDE_CS0") (class "Default")
      (node (ref "CON1") (pin "7") (pinfunction "/CS0_7") (pintype "input"))
      (node (ref "IC7") (pin "205") (pinfunction "PT2B_205") (pintype "bidirectional"))
      (node (ref "X1") (pin "37") (pinfunction "S_37") (pintype "passive"))
    )
    (net (code "134") (name "IDE_CS1") (class "Default")
      (node (ref "CON1") (pin "32") (pinfunction "/CS1_32") (pintype "input"))
      (node (ref "IC7") (pin "206") (pinfunction "PT3B_206") (pintype "bidirectional"))
      (node (ref "X1") (pin "38") (pinfunction "S_38") (pintype "passive"))
    )
    (net (code "135") (name "IDE_D0") (class "Default")
      (node (ref "CON1") (pin "21") (pinfunction "D00_21") (pintype "bidirectional"))
      (node (ref "IC7") (pin "201") (pinfunction "PT4B_201") (pintype "bidirectional"))
      (node (ref "X1") (pin "17") (pinfunction "S_17") (pintype "passive"))
    )
    (net (code "136") (name "IDE_D1") (class "Default")
      (node (ref "CON1") (pin "22") (pinfunction "D01_22") (pintype "bidirectional"))
      (node (ref "IC7") (pin "197") (pinfunction "PT13A_197") (pintype "bidirectional"))
      (node (ref "X1") (pin "15") (pinfunction "S_15") (pintype "passive"))
    )
    (net (code "137") (name "IDE_D2") (class "Default")
      (node (ref "CON1") (pin "23") (pinfunction "D02_23") (pintype "bidirectional"))
      (node (ref "IC7") (pin "195") (pinfunction "PT14A_195") (pintype "bidirectional"))
      (node (ref "X1") (pin "13") (pinfunction "S_13") (pintype "passive"))
    )
    (net (code "138") (name "IDE_D3") (class "Default")
      (node (ref "CON1") (pin "2") (pinfunction "D03_2") (pintype "bidirectional"))
      (node (ref "IC7") (pin "193") (pinfunction "PT14B_193") (pintype "bidirectional"))
      (node (ref "X1") (pin "11") (pinfunction "S_11") (pintype "passive"))
    )
    (net (code "139") (name "IDE_D4") (class "Default")
      (node (ref "CON1") (pin "3") (pinfunction "D04_3") (pintype "bidirectional"))
      (node (ref "IC7") (pin "189") (pinfunction "PT16B_189") (pintype "bidirectional"))
      (node (ref "X1") (pin "9") (pinfunction "S_9") (pintype "passive"))
    )
    (net (code "140") (name "IDE_D5") (class "Default")
      (node (ref "CON1") (pin "4") (pinfunction "D05_4") (pintype "bidirectional"))
      (node (ref "IC7") (pin "187") (pinfunction "PT17B_187") (pintype "bidirectional"))
      (node (ref "X1") (pin "7") (pinfunction "S_7") (pintype "passive"))
    )
    (net (code "141") (name "IDE_D6") (class "Default")
      (node (ref "CON1") (pin "5") (pinfunction "D06_5") (pintype "bidirectional"))
      (node (ref "IC7") (pin "185") (pinfunction "PT19A_185") (pintype "bidirectional"))
      (node (ref "X1") (pin "5") (pinfunction "S_5") (pintype "passive"))
    )
    (net (code "142") (name "IDE_D7") (class "Default")
      (node (ref "CON1") (pin "6") (pinfunction "D07_6") (pintype "bidirectional"))
      (node (ref "IC7") (pin "183") (pinfunction "PT19B_183") (pintype "bidirectional"))
      (node (ref "X1") (pin "3") (pinfunction "S_3") (pintype "passive"))
    )
    (net (code "143") (name "IDE_D8") (class "Default")
      (node (ref "CON1") (pin "47") (pinfunction "D08_47") (pintype "bidirectional"))
      (node (ref "IC7") (pin "184") (pinfunction "PT18B_184") (pintype "bidirectional"))
      (node (ref "X1") (pin "4") (pinfunction "S_4") (pintype "passive"))
    )
    (net (code "144") (name "IDE_D9") (class "Default")
      (node (ref "CON1") (pin "48") (pinfunction "D09_48") (pintype "bidirectional"))
      (node (ref "IC7") (pin "186") (pinfunction "PT18A_186") (pintype "bidirectional"))
      (node (ref "X1") (pin "6") (pinfunction "S_6") (pintype "passive"))
    )
    (net (code "145") (name "IDE_D10") (class "Default")
      (node (ref "CON1") (pin "49") (pinfunction "D10_49") (pintype "bidirectional"))
      (node (ref "IC7") (pin "188") (pinfunction "PT17A_188") (pintype "bidirectional"))
      (node (ref "X1") (pin "8") (pinfunction "S_8") (pintype "passive"))
    )
    (net (code "146") (name "IDE_D11") (class "Default")
      (node (ref "CON1") (pin "27") (pinfunction "D11_27") (pintype "bidirectional"))
      (node (ref "IC7") (pin "192") (pinfunction "PT16A_192") (pintype "bidirectional"))
      (node (ref "X1") (pin "10") (pinfunction "S_10") (pintype "passive"))
    )
    (net (code "147") (name "IDE_D12") (class "Default")
      (node (ref "CON1") (pin "28") (pinfunction "D12_28") (pintype "bidirectional"))
      (node (ref "IC7") (pin "194") (pinfunction "PT15B_194") (pintype "bidirectional"))
      (node (ref "X1") (pin "12") (pinfunction "S_12") (pintype "passive"))
    )
    (net (code "148") (name "IDE_D13") (class "Default")
      (node (ref "CON1") (pin "29") (pinfunction "D13_29") (pintype "bidirectional"))
      (node (ref "IC7") (pin "196") (pinfunction "PT15A_196") (pintype "bidirectional"))
      (node (ref "X1") (pin "14") (pinfunction "S_14") (pintype "passive"))
    )
    (net (code "149") (name "IDE_D14") (class "Default")
      (node (ref "CON1") (pin "30") (pinfunction "D14_30") (pintype "bidirectional"))
      (node (ref "IC7") (pin "198") (pinfunction "PT13B_198") (pintype "bidirectional"))
      (node (ref "X1") (pin "16") (pinfunction "S_16") (pintype "passive"))
    )
    (net (code "150") (name "IDE_D15") (class "Default")
      (node (ref "CON1") (pin "31") (pinfunction "D15_31") (pintype "bidirectional"))
      (node (ref "IC7") (pin "202") (pinfunction "PT4A_202") (pintype "bidirectional"))
      (node (ref "X1") (pin "18") (pinfunction "S_18") (pintype "passive"))
    )
    (net (code "151") (name "IDE_DASP") (class "Default")
      (node (ref "CON1") (pin "45") (pinfunction "/DASP_45") (pintype "bidirectional"))
      (node (ref "R15") (pin "1") (pinfunction "1_1") (pintype "passive"))
      (node (ref "R20") (pin "1") (pinfunction "1_1") (pintype "passive"))
      (node (ref "X1") (pin "34") (pinfunction "S_34") (pintype "passive"))
    )
    (net (code "152") (name "IDE_DMARQ") (class "Default")
      (node (ref "X1") (pin "21") (pinfunction "S_21") (pintype "passive"))
    )
    (net (code "153") (name "IDE_IA0") (class "Default")
      (node (ref "CON1") (pin "20") (pinfunction "A00_20") (pintype "input"))
      (node (ref "IC7") (pin "7") (pinfunction "PL9B_7") (pintype "bidirectional"))
      (node (ref "X1") (pin "35") (pinfunction "S_35") (pintype "passive"))
    )
    (net (code "154") (name "IDE_IA1") (class "Default")
      (node (ref "CON1") (pin "19") (pinfunction "A01_19") (pintype "input"))
      (node (ref "IC7") (pin "6") (pinfunction "PL9A_6") (pintype "bidirectional"))
      (node (ref "X1") (pin "33") (pinfunction "S_33") (pintype "passive"))
    )
    (net (code "155") (name "IDE_IA2") (class "Default")
      (node (ref "CON1") (pin "18") (pinfunction "A02_18") (pintype "input"))
      (node (ref "IC7") (pin "2") (pinfunction "PL2B_2") (pintype "bidirectional"))
      (node (ref "X1") (pin "36") (pinfunction "S_36") (pintype "passive"))
    )
    (net (code "156") (name "IDE_INT") (class "Default")
      (node (ref "CON1") (pin "37") (pinfunction "INTRQ_37") (pintype "output"))
      (node (ref "IC7") (pin "1") (pinfunction "PL2A_1") (pintype "bidirectional"))
      (node (ref "X1") (pin "31") (pinfunction "S_31") (pintype "passive"))
    )
    (net (code "157") (name "IDE_IOCS16") (class "Default")
      (node (ref "CON1") (pin "24") (pinfunction "/IOCS16_24") (pintype "output"))
      (node (ref "R11") (pin "1") (pinfunction "1_1") (pintype "passive"))
      (node (ref "X1") (pin "30") (pinfunction "S_30") (pintype "passive"))
    )
    (net (code "158") (name "IDE_IORDY") (class "Default")
      (node (ref "CON1") (pin "42") (pinfunction "IORDY_42") (pintype "output"))
      (node (ref "R10") (pin "1") (pinfunction "1_1") (pintype "passive"))
      (node (ref "X1") (pin "27") (pinfunction "S_27") (pintype "passive"))
    )
    (net (code "159") (name "IDE_PDIAG") (class "Default")
      (node (ref "CON1") (pin "46") (pinfunction "/PDIAG_46") (pintype "bidirectional"))
      (node (ref "R14") (pin "1") (pinfunction "1_1") (pintype "passive"))
    )
    (net (code "160") (name "IDE_PRESENT") (class "Default")
      (node (ref "CON1") (pin "25") (pinfunction "/CD2_25") (pintype "output"))
      (node (ref "R21") (pin "1") (pinfunction "1_1") (pintype "passive"))
    )
    (net (code "161") (name "IDE_RD") (class "Default")
      (node (ref "CON1") (pin "34") (pinfunction "/IORD_34") (pintype "input"))
      (node (ref "IC7") (pin "207") (pinfunction "PT2A_207") (pintype "bidirectional"))
      (node (ref "X1") (pin "23") (pinfunction "S_23") (pintype "passive"))
    )
    (net (code "162") (name "IDE_SPSYNC") (class "Default")
      (node (ref "X1") (pin "28") (pinfunction "S_28") (pintype "passive"))
    )
    (net (code "163") (name "IDE_VS1") (class "Default")
      (node (ref "CON1") (pin "33") (pinfunction "/VS1_33") (pintype "output"))
      (node (ref "R12") (pin "1") (pinfunction "1_1") (pintype "passive"))
    )
    (net (code "164") (name "IDE_VS2") (class "Default")
      (node (ref "CON1") (pin "40") (pinfunction "/VS2_40") (pintype "output"))
      (node (ref "R13") (pin "1") (pinfunction "1_1") (pintype "passive"))
    )
    (net (code "165") (name "IDE_WR") (class "Default")
      (node (ref "CON1") (pin "35") (pinfunction "/IOWR_35") (pintype "input"))
      (node (ref "IC7") (pin "208") (pinfunction "PT3A_208") (pintype "bidirectional"))
      (node (ref "X1") (pin "25") (pinfunction "S_25") (pintype "passive"))
    )
    (net (code "166") (name "IRQ0") (class "Default")
      (node (ref "IC6") (pin "1") (pinfunction "1/7_1") (pintype "bidirectional"))
      (node (ref "J1") (pin "B21") (pinfunction "B21_B21") (pintype "passive"))
    )
    (net (code "167") (name "IRQ1") (class "Default")
      (node (ref "IC6") (pin "43") (pinfunction "1/3_43") (pintype "bidirectional"))
      (node (ref "J1") (pin "B20") (pinfunction "B20_B20") (pintype "passive"))
    )
    (net (code "168") (name "IRQ2") (class "Default")
      (node (ref "J1") (pin "B19") (pinfunction "B19_B19") (pintype "passive"))
    )
    (net (code "169") (name "IRQ3") (class "Default")
      (node (ref "J1") (pin "B18") (pinfunction "B18_B18") (pintype "passive"))
    )
    (net (code "170") (name "IRQ4") (class "Default")
      (node (ref "J1") (pin "B17") (pinfunction "B17_B17") (pintype "passive"))
    )
    (net (code "171") (name "KEY_CLK") (class "Default")
      (node (ref "D2") (pin "3") (pinfunction "AC_3") (pintype "passive"))
      (node (ref "IC7") (pin "45") (pinfunction "PL24A_45") (pintype "bidirectional"))
      (node (ref "R34") (pin "1") (pinfunction "1_1") (pintype "passive"))
    )
    (net (code "172") (name "KEY_DAT") (class "Default")
      (node (ref "D1") (pin "3") (pinfunction "AC_3") (pintype "passive"))
      (node (ref "IC7") (pin "44") (pinfunction "PL24B_44") (pintype "bidirectional"))
      (node (ref "R33") (pin "1") (pinfunction "1_1") (pintype "passive"))
    )
    (net (code "173") (name "LED_A") (class "Default")
      (node (ref "IC12") (pin "27") (pinfunction "LEDA_27") (pintype "output"))
      (node (ref "J4") (pin "10") (pinfunction "C1_10") (pintype "passive"))
    )
    (net (code "174") (name "LED_B") (class "Default")
      (node (ref "IC12") (pin "26") (pinfunction "LEDB_26") (pintype "output"))
      (node (ref "J4") (pin "8") (pinfunction "C_8") (pintype "passive"))
    )
    (net (code "175") (name "MOUSE_CLK") (class "Default")
      (node (ref "D4") (pin "3") (pinfunction "AC_3") (pintype "passive"))
      (node (ref "IC7") (pin "46") (pinfunction "PL25A_46") (pintype "bidirectional"))
      (node (ref "R36") (pin "1") (pinfunction "1_1") (pintype "passive"))
    )
    (net (code "176") (name "MOUSE_DAT") (class "Default")
      (node (ref "D3") (pin "3") (pinfunction "AC_3") (pintype "passive"))
      (node (ref "IC7") (pin "47") (pinfunction "PL25B_47") (pintype "bidirectional"))
      (node (ref "R35") (pin "1") (pinfunction "1_1") (pintype "passive"))
    )
    (net (code "177") (name "Net-(C54-Pad1)") (class "Default")
      (node (ref "C54") (pin "1") (pinfunction "1_1") (pintype "passive"))
      (node (ref "R39") (pin "2") (pinfunction "2_2") (pintype "passive"))
      (node (ref "X2") (pin "5") (pinfunction "5_5") (pintype "passive"))
    )
    (net (code "178") (name "Net-(C55-Pad1)") (class "Default")
      (node (ref "C55") (pin "1") (pinfunction "1_1") (pintype "passive"))
      (node (ref "R40") (pin "2") (pinfunction "2_2") (pintype "passive"))
      (node (ref "X2") (pin "2") (pinfunction "2_2") (pintype "passive"))
    )
    (net (code "179") (name "Net-(C66-Pad2)") (class "Default")
      (node (ref "C66") (pin "2") (pinfunction "2_2") (pintype "passive"))
      (node (ref "R45") (pin "1") (pinfunction "1_1") (pintype "passive"))
      (node (ref "R47") (pin "2") (pinfunction "2_2") (pintype "passive"))
    )
    (net (code "180") (name "Net-(CON1A-{slash}ATASEL)") (class "Default")
      (node (ref "CON1") (pin "9") (pinfunction "/ATASEL_9") (pintype "input"))
      (node (ref "R17") (pin "1") (pinfunction "1_1") (pintype "passive"))
    )
    (net (code "181") (name "Net-(CON1A-{slash}CD1)") (class "Default")
      (node (ref "CON1") (pin "26") (pinfunction "/CD1_26") (pintype "output"))
      (node (ref "JP19") (pin "1") (pinfunction "1_1") (pintype "passive"))
    )
    (net (code "182") (name "Net-(CON1A-{slash}CSEL)") (class "Default")
      (node (ref "CON1") (pin "39") (pinfunction "/CSEL_39") (pintype "input"))
      (node (ref "R18") (pin "1") (pinfunction "1_1") (pintype "passive"))
    )
    (net (code "183") (name "Net-(CON1A-{slash}INPACK)") (class "Default")
      (node (ref "CON1") (pin "43") (pinfunction "/INPACK_43") (pintype "output"))
      (node (ref "JP20") (pin "1") (pinfunction "1_1") (pintype "passive"))
    )
    (net (code "184") (name "Net-(CON1A-{slash}RESET)") (class "Default")
      (node (ref "CON1") (pin "41") (pinfunction "/RESET_41") (pintype "input"))
      (node (ref "JP17") (pin "1") (pinfunction "1_1") (pintype "passive"))
      (node (ref "R19") (pin "1") (pinfunction "1_1") (pintype "passive"))
    )
    (net (code "185") (name "Net-(IC1A-G)") (class "Default")
      (node (ref "IC1") (pin "19") (pinfunction "G_19") (pintype "input"))
      (node (ref "IC2") (pin "19") (pinfunction "G_19") (pintype "input"))
      (node (ref "JP4") (pin "1") (pinfunction "1_1") (pintype "passive"))
      (node (ref "R4") (pin "2") (pinfunction "2_2") (pintype "passive"))
    )
    (net (code "186") (name "Net-(IC3A-DIR)") (class "Default")
      (node (ref "IC3") (pin "1") (pinfunction "DIR_1") (pintype "input"))
      (node (ref "IC4") (pin "1") (pinfunction "DIR_1") (pintype "input"))
      (node (ref "IC5") (pin "1") (pinfunction "DIR_1") (pintype "input"))
      (node (ref "JP5") (pin "1") (pinfunction "1_1") (pintype "passive"))
      (node (ref "R5") (pin "2") (pinfunction "2_2") (pintype "passive"))
    )
    (net (code "187") (name "Net-(IC6-1{slash}13)") (class "Default")
      (node (ref "IC6") (pin "12") (pinfunction "1/13_12") (pintype "bidirectional"))
      (node (ref "JP2") (pin "1") (pinfunction "1_1") (pintype "passive"))
    )
    (net (code "188") (name "Net-(IC6-2{slash}2)") (class "Default")
      (node (ref "IC6") (pin "38") (pinfunction "2/2_38") (pintype "bidirectional"))
      (node (ref "JP6") (pin "1") (pinfunction "1_1") (pintype "passive"))
    )
    (net (code "189") (name "Net-(IC6-2{slash}5)") (class "Default")
      (node (ref "IC6") (pin "34") (pinfunction "2/5_34") (pintype "bidirectional"))
      (node (ref "JP7") (pin "1") (pinfunction "1_1") (pintype "passive"))
    )
    (net (code "190") (name "Net-(IC7B-TOE)") (class "Default")
      (node (ref "IC7") (pin "28") (pinfunction "TOE_28") (pintype "input"))
      (node (ref "R7") (pin "1") (pinfunction "1_1") (pintype "passive"))
    )
    (net (code "191") (name "Net-(IC7D-PT20A)") (class "Default")
      (node (ref "IC7") (pin "180") (pinfunction "PT20A_180") (pintype "bidirectional"))
      (node (ref "JP14") (pin "1") (pinfunction "1_1") (pintype "passive"))
    )
    (net (code "192") (name "Net-(IC7E-PR11B)") (class "Default")
      (node (ref "IC7") (pin "145") (pinfunction "PR11B_145") (pintype "bidirectional"))
      (node (ref "JP13") (pin "1") (pinfunction "1_1") (pintype "passive"))
    )
    (net (code "193") (name "Net-(IC7J-PL16A)") (class "Default")
      (node (ref "IC7") (pin "22") (pinfunction "PL16A_22") (pintype "bidirectional"))
      (node (ref "JP10") (pin "1") (pinfunction "1_1") (pintype "passive"))
    )
    (net (code "194") (name "Net-(IC11A-C1+)") (class "Default")
      (node (ref "C50") (pin "2") (pinfunction "2_2") (pintype "passive"))
      (node (ref "IC11") (pin "1") (pinfunction "C1+_1") (pintype "bidirectional"))
    )
    (net (code "195") (name "Net-(IC11A-C1-)") (class "Default")
      (node (ref "C50") (pin "1") (pinfunction "1_1") (pintype "passive"))
      (node (ref "IC11") (pin "3") (pinfunction "C1-_3") (pintype "bidirectional"))
    )
    (net (code "196") (name "Net-(IC11A-C2+)") (class "Default")
      (node (ref "C49") (pin "2") (pinfunction "2_2") (pintype "passive"))
      (node (ref "IC11") (pin "4") (pinfunction "C2+_4") (pintype "bidirectional"))
    )
    (net (code "197") (name "Net-(IC11A-C2-)") (class "Default")
      (node (ref "C49") (pin "1") (pinfunction "1_1") (pintype "passive"))
      (node (ref "IC11") (pin "5") (pinfunction "C2-_5") (pintype "bidirectional"))
    )
    (net (code "198") (name "Net-(IC11A-R1IN)") (class "Default")
      (node (ref "IC11") (pin "13") (pinfunction "R1IN_13") (pintype "input"))
      (node (ref "JP18") (pin "8") (pinfunction "8_8") (pintype "passive"))
    )
    (net (code "199") (name "Net-(IC11A-R2IN)") (class "Default")
      (node (ref "IC11") (pin "8") (pinfunction "R2IN_8") (pintype "input"))
      (node (ref "JP18") (pin "2") (pinfunction "2_2") (pintype "passive"))
    )
    (net (code "200") (name "Net-(IC11A-T1OUT)") (class "Default")
      (node (ref "IC11") (pin "14") (pinfunction "T1OUT_14") (pintype "output"))
      (node (ref "JP18") (pin "7") (pinfunction "7_7") (pintype "passive"))
    )
    (net (code "201") (name "Net-(IC11A-T2OUT)") (class "Default")
      (node (ref "IC11") (pin "7") (pinfunction "T2OUT_7") (pintype "output"))
      (node (ref "JP18") (pin "3") (pinfunction "3_3") (pintype "passive"))
    )
    (net (code "202") (name "Net-(IC11A-V+)") (class "Default")
      (node (ref "C51") (pin "2") (pinfunction "2_2") (pintype "passive"))
      (node (ref "IC11") (pin "2") (pinfunction "V+_2") (pintype "bidirectional"))
    )
    (net (code "203") (name "Net-(IC11A-V-)") (class "Default")
      (node (ref "C52") (pin "1") (pinfunction "1_1") (pintype "passive"))
      (node (ref "IC11") (pin "6") (pinfunction "V-_6") (pintype "bidirectional"))
    )
    (net (code "204") (name "Net-(IC12-CLKOUT)") (class "Default")
      (node (ref "IC12") (pin "3") (pinfunction "CLKOUT_3") (pintype "output"))
      (node (ref "JP29") (pin "1") (pinfunction "1_1") (pintype "passive"))
    )
    (net (code "205") (name "Net-(IC12-OSC1)") (class "Default")
      (node (ref "C63") (pin "2") (pinfunction "2_2") (pintype "passive"))
      (node (ref "IC12") (pin "23") (pinfunction "OSC1_23") (pintype "input"))
      (node (ref "Q1") (pin "2") (pinfunction "2_2") (pintype "passive"))
    )
    (net (code "206") (name "Net-(IC12-OSC2)") (class "Default")
      (node (ref "C61") (pin "2") (pinfunction "2_2") (pintype "passive"))
      (node (ref "IC12") (pin "24") (pinfunction "OSC2_24") (pintype "output"))
      (node (ref "Q1") (pin "1") (pinfunction "1_1") (pintype "passive"))
    )
    (net (code "207") (name "Net-(IC12-RBIAS)") (class "Default")
      (node (ref "IC12") (pin "14") (pinfunction "RBIAS_14") (pintype "input"))
      (node (ref "R44") (pin "2") (pinfunction "2_2") (pintype "passive"))
    )
    (net (code "208") (name "Net-(IC12-VCAP)") (class "Default")
      (node (ref "C59") (pin "+") (pinfunction "+_+") (pintype "passive"))
      (node (ref "IC12") (pin "1") (pinfunction "VCAP_1") (pintype "input"))
    )
    (net (code "209") (name "Net-(IC12-~{RESET})") (class "Default")
      (node (ref "IC12") (pin "10") (pinfunction "~{RESET}_10") (pintype "input"))
      (node (ref "JP31") (pin "1") (pinfunction "1_1") (pintype "passive"))
      (node (ref "R43") (pin "1") (pinfunction "1_1") (pintype "passive"))
    )
    (net (code "210") (name "Net-(J2-COM_TERM)") (class "Default")
      (node (ref "J2") (pin "CD") (pinfunction "COM_TERM_CD") (pintype "passive"))
      (node (ref "JP27") (pin "1") (pinfunction "1_1") (pintype "passive"))
    )
    (net (code "211") (name "Net-(J2-Pad8)") (class "Default")
      (node (ref "J2") (pin "8") (pinfunction "8_8") (pintype "input"))
      (node (ref "JP25") (pin "1") (pinfunction "1_1") (pintype "passive"))
    )
    (net (code "212") (name "Net-(J2-Pad9)") (class "Default")
      (node (ref "J2") (pin "9") (pinfunction "9_9") (pintype "input"))
      (node (ref "JP26") (pin "1") (pinfunction "1_1") (pintype "passive"))
    )
    (net (code "213") (name "Net-(J2-WRITE_PROT)") (class "Default")
      (node (ref "J2") (pin "WP") (pinfunction "WRITE_PROT_WP") (pintype "passive"))
      (node (ref "JP28") (pin "1") (pinfunction "1_1") (pintype "passive"))
    )
    (net (code "214") (name "Net-(J3-Pad1)") (class "Default")
      (node (ref "J3") (pin "1") (pinfunction "1_1") (pintype "passive"))
      (node (ref "R22") (pin "2") (pinfunction "2_2") (pintype "passive"))
      (node (ref "R23") (pin "2") (pinfunction "2_2") (pintype "passive"))
      (node (ref "R24") (pin "2") (pinfunction "2_2") (pintype "passive"))
    )
    (net (code "215") (name "Net-(J3-Pad2)") (class "Default")
      (node (ref "J3") (pin "2") (pinfunction "2_2") (pintype "passive"))
      (node (ref "R25") (pin "2") (pinfunction "2_2") (pintype "passive"))
      (node (ref "R26") (pin "2") (pinfunction "2_2") (pintype "passive"))
      (node (ref "R27") (pin "2") (pinfunction "2_2") (pintype "passive"))
    )
    (net (code "216") (name "Net-(J3-Pad3)") (class "Default")
      (node (ref "J3") (pin "3") (pinfunction "3_3") (pintype "passive"))
      (node (ref "R28") (pin "2") (pinfunction "2_2") (pintype "passive"))
      (node (ref "R29") (pin "2") (pinfunction "2_2") (pintype "passive"))
      (node (ref "R30") (pin "2") (pinfunction "2_2") (pintype "passive"))
    )
    (net (code "217") (name "Net-(J3-Pad13)") (class "Default")
      (node (ref "J3") (pin "13") (pinfunction "13_13") (pintype "passive"))
      (node (ref "R32") (pin "1") (pinfunction "1_1") (pintype "passive"))
    )
    (net (code "218") (name "Net-(J3-Pad14)") (class "Default")
      (node (ref "J3") (pin "14") (pinfunction "14_14") (pintype "passive"))
      (node (ref "R31") (pin "1") (pinfunction "1_1") (pintype "passive"))
    )
    (net (code "219") (name "Net-(J3G-1)") (class "Default")
      (node (ref "J3") (pin "1-1") (pinfunction "1_1-1") (pintype "passive"))
      (node (ref "R33") (pin "2") (pinfunction "2_2") (pintype "passive"))
      (node (ref "R37") (pin "2") (pinfunction "2_2") (pintype "passive"))
    )
    (net (code "220") (name "Net-(J3G-5)") (class "Default")
      (node (ref "J3") (pin "1-5") (pinfunction "5_1-5") (pintype "passive"))
      (node (ref "R34") (pin "2") (pinfunction "2_2") (pintype "passive"))
      (node (ref "R41") (pin "2") (pinfunction "2_2") (pintype "passive"))
    )
    (net (code "221") (name "Net-(J3H-1)") (class "Default")
      (node (ref "J3") (pin "2-1") (pinfunction "1_2-1") (pintype "passive"))
      (node (ref "R35") (pin "2") (pinfunction "2_2") (pintype "passive"))
      (node (ref "R38") (pin "2") (pinfunction "2_2") (pintype "passive"))
    )
    (net (code "222") (name "Net-(J3H-5)") (class "Default")
      (node (ref "J3") (pin "2-5") (pinfunction "5_2-5") (pintype "passive"))
      (node (ref "R36") (pin "2") (pinfunction "2_2") (pintype "passive"))
      (node (ref "R42") (pin "2") (pinfunction "2_2") (pintype "passive"))
    )
    (net (code "223") (name "Net-(J4-A)") (class "Default")
      (node (ref "J4") (pin "7") (pinfunction "A_7") (pintype "passive"))
      (node (ref "R49") (pin "1") (pinfunction "1_1") (pintype "passive"))
    )
    (net (code "224") (name "Net-(J4-A1)") (class "Default")
      (node (ref "J4") (pin "9") (pinfunction "A1_9") (pintype "passive"))
      (node (ref "R50") (pin "1") (pinfunction "1_1") (pintype "passive"))
    )
    (net (code "225") (name "Net-(J4-TCT)") (class "Default")
      (node (ref "C67") (pin "2") (pinfunction "2_2") (pintype "passive"))
      (node (ref "J4") (pin "1") (pinfunction "TCT_1") (pintype "passive"))
      (node (ref "L1") (pin "2") (pinfunction "2_2") (pintype "passive"))
      (node (ref "R46") (pin "1") (pinfunction "1_1") (pintype "passive"))
      (node (ref "R48") (pin "2") (pinfunction "2_2") (pintype "passive"))
    )
    (net (code "226") (name "Net-(LED1-PadA)") (class "Default")
      (node (ref "LED1") (pin "A") (pinfunction "A_A") (pintype "passive"))
      (node (ref "R9") (pin "1") (pinfunction "1_1") (pintype "passive"))
    )
    (net (code "227") (name "Net-(LED2-PadC)") (class "Default")
      (node (ref "LED2") (pin "C") (pinfunction "C_C") (pintype "passive"))
      (node (ref "R20") (pin "2") (pinfunction "2_2") (pintype "passive"))
    )
    (net (code "228") (name "Net-(LED3-PadC)") (class "Default")
      (node (ref "LED3") (pin "C") (pinfunction "C_C") (pintype "passive"))
      (node (ref "R21") (pin "2") (pinfunction "2_2") (pintype "passive"))
    )
    (net (code "229") (name "Net-(QG1-OUT)") (class "Default")
      (node (ref "QG1") (pin "5") (pinfunction "OUT_5") (pintype "output"))
      (node (ref "R6") (pin "2") (pinfunction "2_2") (pintype "passive"))
    )
    (net (code "230") (name "RAM0_CE") (class "Default")
      (node (ref "IC7") (pin "75") (pinfunction "PB18A_75") (pintype "bidirectional"))
      (node (ref "IC8") (pin "6") (pinfunction "~{CE}_6") (pintype "input"))
    )
    (net (code "231") (name "RAM1_CE") (class "Default")
      (node (ref "IC7") (pin "74") (pinfunction "PB17B_74") (pintype "bidirectional"))
      (node (ref "IC9") (pin "6") (pinfunction "~{CE}_6") (pintype "input"))
    )
    (net (code "232") (name "RAM_A0") (class "Default")
      (node (ref "IC7") (pin "84") (pinfunction "PB21B_84") (pintype "bidirectional"))
      (node (ref "IC8") (pin "23") (pinfunction "A10_23") (pintype "input"))
      (node (ref "IC9") (pin "27") (pinfunction "A14_27") (pintype "input"))
    )
    (net (code "233") (name "RAM_A1") (class "Default")
      (node (ref "IC7") (pin "85") (pinfunction "PB22A_85") (pintype "bidirectional"))
      (node (ref "IC8") (pin "24") (pinfunction "A11_24") (pintype "input"))
      (node (ref "IC9") (pin "26") (pinfunction "A13_26") (pintype "input"))
    )
    (net (code "234") (name "RAM_A2") (class "Default")
      (node (ref "IC7") (pin "86") (pinfunction "PB23A_86") (pintype "bidirectional"))
      (node (ref "IC8") (pin "25") (pinfunction "A12_25") (pintype "input"))
      (node (ref "IC9") (pin "25") (pinfunction "A12_25") (pintype "input"))
    )
    (net (code "235") (name "RAM_A3") (class "Default")
      (node (ref "IC7") (pin "87") (pinfunction "PB22B_87") (pintype "bidirectional"))
      (node (ref "IC8") (pin "26") (pinfunction "A13_26") (pintype "input"))
      (node (ref "IC9") (pin "24") (pinfunction "A11_24") (pintype "input"))
    )
    (net (code "236") (name "RAM_A4") (class "Default")
      (node (ref "IC7") (pin "88") (pinfunction "PB23B_88") (pintype "bidirectional"))
      (node (ref "IC8") (pin "27") (pinfunction "A14_27") (pintype "input"))
      (node (ref "IC9") (pin "23") (pinfunction "A10_23") (pintype "input"))
    )
    (net (code "237") (name "RAM_A5") (class "Default")
      (node (ref "IC7") (pin "78") (pinfunction "PB19B_78") (pintype "bidirectional"))
      (node (ref "IC8") (pin "44") (pinfunction "A17_44") (pintype "input"))
      (node (ref "IC9") (pin "42") (pinfunction "A15_42") (pintype "input"))
    )
    (net (code "238") (name "RAM_A6") (class "Default")
      (node (ref "IC7") (pin "77") (pinfunction "PB18B_77") (pintype "bidirectional"))
      (node (ref "IC8") (pin "43") (pinfunction "A16_43") (pintype "input"))
      (node (ref "IC9") (pin "43") (pinfunction "A16_43") (pintype "input"))
    )
    (net (code "239") (name "RAM_A7") (class "Default")
      (node (ref "IC7") (pin "76") (pinfunction "PB19A_76") (pintype "bidirectional"))
      (node (ref "IC8") (pin "42") (pinfunction "A15_42") (pintype "input"))
      (node (ref "IC9") (pin "44") (pinfunction "A17_44") (pintype "input"))
    )
    (net (code "240") (name "RAM_A8") (class "Default")
      (node (ref "IC7") (pin "104") (pinfunction "PB32B_104") (pintype "bidirectional"))
      (node (ref "IC8") (pin "22") (pinfunction "A9_22") (pintype "input"))
      (node (ref "IC9") (pin "22") (pinfunction "A9_22") (pintype "input"))
    )
    (net (code "241") (name "RAM_A9") (class "Default")
      (node (ref "IC7") (pin "91") (pinfunction "PB24A_91") (pintype "bidirectional"))
      (node (ref "IC8") (pin "1") (pinfunction "A0_1") (pintype "input"))
      (node (ref "IC9") (pin "1") (pinfunction "A0_1") (pintype "input"))
    )
    (net (code "242") (name "RAM_A10") (class "Default")
      (node (ref "IC7") (pin "92") (pinfunction "PB25A_92") (pintype "bidirectional"))
      (node (ref "IC8") (pin "2") (pinfunction "A1_2") (pintype "input"))
      (node (ref "IC9") (pin "2") (pinfunction "A1_2") (pintype "input"))
    )
    (net (code "243") (name "RAM_A11") (class "Default")
      (node (ref "IC7") (pin "93") (pinfunction "PB24B_93") (pintype "bidirectional"))
      (node (ref "IC8") (pin "3") (pinfunction "A2_3") (pintype "input"))
      (node (ref "IC9") (pin "3") (pinfunction "A2_3") (pintype "input"))
    )
    (net (code "244") (name "RAM_A12") (class "Default")
      (node (ref "IC7") (pin "94") (pinfunction "PB25B_94") (pintype "bidirectional"))
      (node (ref "IC8") (pin "4") (pinfunction "A3_4") (pintype "input"))
      (node (ref "IC9") (pin "4") (pinfunction "A3_4") (pintype "input"))
    )
    (net (code "245") (name "RAM_A13") (class "Default")
      (node (ref "IC7") (pin "97") (pinfunction "PB30A_97") (pintype "bidirectional"))
      (node (ref "IC8") (pin "5") (pinfunction "A4_5") (pintype "input"))
      (node (ref "IC9") (pin "5") (pinfunction "A4_5") (pintype "input"))
    )
    (net (code "246") (name "RAM_A14") (class "Default")
      (node (ref "IC7") (pin "98") (pinfunction "PB30B_98") (pintype "bidirectional"))
      (node (ref "IC8") (pin "18") (pinfunction "A5_18") (pintype "input"))
      (node (ref "IC9") (pin "18") (pinfunction "A5_18") (pintype "input"))
    )
    (net (code "247") (name "RAM_A15") (class "Default")
      (node (ref "IC7") (pin "101") (pinfunction "PB31A_101") (pintype "bidirectional"))
      (node (ref "IC8") (pin "19") (pinfunction "A6_19") (pintype "input"))
      (node (ref "IC9") (pin "19") (pinfunction "A6_19") (pintype "input"))
    )
    (net (code "248") (name "RAM_A16") (class "Default")
      (node (ref "IC7") (pin "102") (pinfunction "PB32A_102") (pintype "bidirectional"))
      (node (ref "IC8") (pin "20") (pinfunction "A7_20") (pintype "input"))
      (node (ref "IC9") (pin "20") (pinfunction "A7_20") (pintype "input"))
    )
    (net (code "249") (name "RAM_A17") (class "Default")
      (node (ref "IC7") (pin "103") (pinfunction "PB31B_103") (pintype "bidirectional"))
      (node (ref "IC8") (pin "21") (pinfunction "A8_21") (pintype "input"))
      (node (ref "IC9") (pin "21") (pinfunction "A8_21") (pintype "input"))
    )
    (net (code "250") (name "RAM_A18") (class "Default")
      (node (ref "IC7") (pin "134") (pinfunction "PR16B_134") (pintype "bidirectional"))
      (node (ref "IC8") (pin "28") (pinfunction "A18_28") (pintype "input"))
      (node (ref "IC9") (pin "28") (pinfunction "A18_28") (pintype "input"))
    )
    (net (code "251") (name "RAM_BHE") (class "Default")
      (node (ref "IC7") (pin "82") (pinfunction "PB20B_82") (pintype "bidirectional"))
      (node (ref "IC8") (pin "40") (pinfunction "~{BHE}_40") (pintype "output"))
      (node (ref "IC9") (pin "40") (pinfunction "~{BHE}_40") (pintype "output"))
    )
    (net (code "252") (name "RAM_BLE") (class "Default")
      (node (ref "IC7") (pin "83") (pinfunction "PB21A_83") (pintype "bidirectional"))
      (node (ref "IC8") (pin "39") (pinfunction "~{BLE}_39") (pintype "output"))
      (node (ref "IC9") (pin "39") (pinfunction "~{BLE}_39") (pintype "output"))
    )
    (net (code "253") (name "RAM_D0") (class "Default")
      (node (ref "IC7") (pin "52") (pinfunction "PL32B_52") (pintype "bidirectional"))
      (node (ref "IC8") (pin "7") (pinfunction "D0_7") (pintype "tri_state"))
      (node (ref "IC9") (pin "7") (pinfunction "D0_7") (pintype "tri_state"))
    )
    (net (code "254") (name "RAM_D1") (class "Default")
      (node (ref "IC7") (pin "51") (pinfunction "PL32A_51") (pintype "bidirectional"))
      (node (ref "IC8") (pin "8") (pinfunction "D1_8") (pintype "tri_state"))
      (node (ref "IC9") (pin "8") (pinfunction "D1_8") (pintype "tri_state"))
    )
    (net (code "255") (name "RAM_D2") (class "Default")
      (node (ref "IC7") (pin "53") (pinfunction "PB3A_53") (pintype "bidirectional"))
      (node (ref "IC8") (pin "9") (pinfunction "D2_9") (pintype "tri_state"))
      (node (ref "IC9") (pin "9") (pinfunction "D2_9") (pintype "tri_state"))
    )
    (net (code "256") (name "RAM_D3") (class "Default")
      (node (ref "IC7") (pin "54") (pinfunction "PB2A_54") (pintype "bidirectional"))
      (node (ref "IC8") (pin "10") (pinfunction "D3_10") (pintype "tri_state"))
      (node (ref "IC9") (pin "10") (pinfunction "D3_10") (pintype "tri_state"))
    )
    (net (code "257") (name "RAM_D4") (class "Default")
      (node (ref "IC7") (pin "55") (pinfunction "PB3B_55") (pintype "bidirectional"))
      (node (ref "IC8") (pin "13") (pinfunction "D4_13") (pintype "tri_state"))
      (node (ref "IC9") (pin "13") (pinfunction "D4_13") (pintype "tri_state"))
    )
    (net (code "258") (name "RAM_D5") (class "Default")
      (node (ref "IC7") (pin "56") (pinfunction "PB2B_56") (pintype "bidirectional"))
      (node (ref "IC8") (pin "14") (pinfunction "D5_14") (pintype "tri_state"))
      (node (ref "IC9") (pin "14") (pinfunction "D5_14") (pintype "tri_state"))
    )
    (net (code "259") (name "RAM_D6") (class "Default")
      (node (ref "IC7") (pin "59") (pinfunction "PB4A_59") (pintype "bidirectional"))
      (node (ref "IC8") (pin "15") (pinfunction "D6_15") (pintype "tri_state"))
      (node (ref "IC9") (pin "15") (pinfunction "D6_15") (pintype "tri_state"))
    )
    (net (code "260") (name "RAM_D7") (class "Default")
      (node (ref "IC7") (pin "60") (pinfunction "PB4B_60") (pintype "bidirectional"))
      (node (ref "IC8") (pin "16") (pinfunction "D7_16") (pintype "tri_state"))
      (node (ref "IC9") (pin "16") (pinfunction "D7_16") (pintype "tri_state"))
    )
    (net (code "261") (name "RAM_D8") (class "Default")
      (node (ref "IC7") (pin "63") (pinfunction "PB13B_63") (pintype "bidirectional"))
      (node (ref "IC8") (pin "29") (pinfunction "D8_29") (pintype "tri_state"))
      (node (ref "IC9") (pin "29") (pinfunction "D8_29") (pintype "tri_state"))
    )
    (net (code "262") (name "RAM_D9") (class "Default")
      (node (ref "IC7") (pin "64") (pinfunction "PB13A_64") (pintype "bidirectional"))
      (node (ref "IC8") (pin "30") (pinfunction "D9_30") (pintype "tri_state"))
      (node (ref "IC9") (pin "30") (pinfunction "D9_30") (pintype "tri_state"))
    )
    (net (code "263") (name "RAM_D10") (class "Default")
      (node (ref "IC7") (pin "65") (pinfunction "PB15A_65") (pintype "bidirectional"))
      (node (ref "IC8") (pin "31") (pinfunction "D10_31") (pintype "tri_state"))
      (node (ref "IC9") (pin "31") (pinfunction "D10_31") (pintype "tri_state"))
    )
    (net (code "264") (name "RAM_D11") (class "Default")
      (node (ref "IC7") (pin "66") (pinfunction "PB14A_66") (pintype "bidirectional"))
      (node (ref "IC8") (pin "32") (pinfunction "D11_32") (pintype "tri_state"))
      (node (ref "IC9") (pin "32") (pinfunction "D11_32") (pintype "tri_state"))
    )
    (net (code "265") (name "RAM_D12") (class "Default")
      (node (ref "IC7") (pin "67") (pinfunction "PB15B_67") (pintype "bidirectional"))
      (node (ref "IC8") (pin "35") (pinfunction "D12_35") (pintype "tri_state"))
      (node (ref "IC9") (pin "35") (pinfunction "D12_35") (pintype "tri_state"))
    )
    (net (code "266") (name "RAM_D13") (class "Default")
      (node (ref "IC7") (pin "68") (pinfunction "PB14B_68") (pintype "bidirectional"))
      (node (ref "IC8") (pin "36") (pinfunction "D13_36") (pintype "tri_state"))
      (node (ref "IC9") (pin "36") (pinfunction "D13_36") (pintype "tri_state"))
    )
    (net (code "267") (name "RAM_D14") (class "Default")
      (node (ref "IC7") (pin "69") (pinfunction "PB16A_69") (pintype "bidirectional"))
      (node (ref "IC8") (pin "37") (pinfunction "D14_37") (pintype "tri_state"))
      (node (ref "IC9") (pin "37") (pinfunction "D14_37") (pintype "tri_state"))
    )
    (net (code "268") (name "RAM_D15") (class "Default")
      (node (ref "IC7") (pin "72") (pinfunction "PB16B_72") (pintype "bidirectional"))
      (node (ref "IC8") (pin "38") (pinfunction "D15_38") (pintype "tri_state"))
      (node (ref "IC9") (pin "38") (pinfunction "D15_38") (pintype "tri_state"))
    )
    (net (code "269") (name "RAM_OE") (class "Default")
      (node (ref "IC7") (pin "81") (pinfunction "PB20A_81") (pintype "bidirectional"))
      (node (ref "IC8") (pin "41") (pinfunction "~{OE}_41") (pintype "input"))
      (node (ref "IC9") (pin "41") (pinfunction "~{OE}_41") (pintype "input"))
    )
    (net (code "270") (name "RAM_WE") (class "Default")
      (node (ref "IC7") (pin "73") (pinfunction "PB17A_73") (pintype "bidirectional"))
      (node (ref "IC8") (pin "17") (pinfunction "~{WE}_17") (pintype "input"))
      (node (ref "IC9") (pin "17") (pinfunction "~{WE}_17") (pintype "input"))
    )
    (net (code "271") (name "S1_CTS") (class "Default")
      (node (ref "IC11") (pin "12") (pinfunction "R1OUT_12") (pintype "output"))
      (node (ref "IC7") (pin "12") (pinfunction "PL11B_12") (pintype "bidirectional"))
    )
    (net (code "272") (name "S1_RTS") (class "Default")
      (node (ref "IC11") (pin "11") (pinfunction "T1IN_11") (pintype "input"))
      (node (ref "IC7") (pin "11") (pinfunction "PL12A_11") (pintype "bidirectional"))
    )
    (net (code "273") (name "S1_RXD") (class "Default")
      (node (ref "IC11") (pin "9") (pinfunction "R2OUT_9") (pintype "output"))
      (node (ref "IC7") (pin "10") (pinfunction "PL10B_10") (pintype "bidirectional"))
    )
    (net (code "274") (name "S1_TXD") (class "Default")
      (node (ref "IC11") (pin "10") (pinfunction "T2IN_10") (pintype "input"))
      (node (ref "IC7") (pin "9") (pinfunction "PL11A_9") (pintype "bidirectional"))
    )
    (net (code "275") (name "SD0_CS") (class "Default")
      (node (ref "IC7") (pin "18") (pinfunction "PL13B_18") (pintype "bidirectional"))
      (node (ref "J2") (pin "1") (pinfunction "1_1") (pintype "input"))
      (node (ref "JP21") (pin "1") (pinfunction "1_1") (pintype "passive"))
    )
    (net (code "276") (name "SD0_DI") (class "Default")
      (node (ref "IC12") (pin "7") (pinfunction "SI_7") (pintype "input"))
      (node (ref "IC7") (pin "17") (pinfunction "PL14A_17") (pintype "bidirectional"))
      (node (ref "J2") (pin "2") (pinfunction "2_2") (pintype "input"))
      (node (ref "JP22") (pin "1") (pinfunction "1_1") (pintype "passive"))
    )
    (net (code "277") (name "SD0_DO") (class "Default")
      (node (ref "IC12") (pin "6") (pinfunction "SO_6") (pintype "output"))
      (node (ref "IC7") (pin "13") (pinfunction "PL12B_13") (pintype "bidirectional"))
      (node (ref "J2") (pin "7") (pinfunction "7_7") (pintype "input"))
      (node (ref "JP24") (pin "1") (pinfunction "1_1") (pintype "passive"))
    )
    (net (code "278") (name "SD0_SCLK") (class "Default")
      (node (ref "IC12") (pin "8") (pinfunction "SCK_8") (pintype "input"))
      (node (ref "IC7") (pin "15") (pinfunction "PL13A_15") (pintype "bidirectional"))
      (node (ref "J2") (pin "5") (pinfunction "5_5") (pintype "input"))
      (node (ref "JP23") (pin "1") (pinfunction "1_1") (pintype "passive"))
    )
    (net (code "279") (name "SIZ0") (class "Default")
      (node (ref "IC6") (pin "6") (pinfunction "1/10_6") (pintype "bidirectional"))
      (node (ref "J1") (pin "B29") (pinfunction "B29_B29") (pintype "passive"))
    )
    (net (code "280") (name "SIZ1") (class "Default")
      (node (ref "IC6") (pin "5") (pinfunction "1/9_5") (pintype "bidirectional"))
      (node (ref "J1") (pin "B28") (pinfunction "B28_B28") (pintype "passive"))
    )
    (net (code "281") (name "TCK") (class "Default")
      (node (ref "IC6") (pin "11") (pinfunction "TCK_11") (pintype "input"))
      (node (ref "SV1") (pin "3") (pinfunction "3_3") (pintype "passive"))
    )
    (net (code "282") (name "TDI") (class "Default")
      (node (ref "IC6") (pin "9") (pinfunction "TDI_9") (pintype "input"))
      (node (ref "SV1") (pin "5") (pinfunction "5_5") (pintype "passive"))
    )
    (net (code "283") (name "TDO") (class "Default")
      (node (ref "IC6") (pin "24") (pinfunction "TDO_24") (pintype "output"))
      (node (ref "SV1") (pin "4") (pinfunction "4_4") (pintype "passive"))
    )
    (net (code "284") (name "TMS") (class "Default")
      (node (ref "IC6") (pin "10") (pinfunction "TMS_10") (pintype "input"))
      (node (ref "SV1") (pin "6") (pinfunction "6_6") (pintype "passive"))
    )
    (net (code "285") (name "TPIN+") (class "Default")
      (node (ref "IC12") (pin "13") (pinfunction "TPIN+_13") (pintype "input"))
      (node (ref "J4") (pin "4") (pinfunction "RD+_4") (pintype "passive"))
      (node (ref "R45") (pin "2") (pinfunction "2_2") (pintype "passive"))
    )
    (net (code "286") (name "TPIN-") (class "Default")
      (node (ref "IC12") (pin "12") (pinfunction "TPIN-_12") (pintype "input"))
      (node (ref "J4") (pin "5") (pinfunction "RD-_5") (pintype "passive"))
      (node (ref "R47") (pin "1") (pinfunction "1_1") (pintype "passive"))
    )
    (net (code "287") (name "TPOUT+") (class "Default")
      (node (ref "IC12") (pin "17") (pinfunction "TPOUT+_17") (pintype "output"))
      (node (ref "J4") (pin "2") (pinfunction "TD+_2") (pintype "passive"))
      (node (ref "R48") (pin "1") (pinfunction "1_1") (pintype "passive"))
    )
    (net (code "288") (name "TPOUT-") (class "Default")
      (node (ref "IC12") (pin "16") (pinfunction "TPOUT-_16") (pintype "output"))
      (node (ref "J4") (pin "3") (pinfunction "TD-_3") (pintype "passive"))
      (node (ref "R46") (pin "2") (pinfunction "2_2") (pintype "passive"))
    )
    (net (code "289") (name "VCC") (class "Default")
      (node (ref "C1") (pin "1") (pinfunction "1_1") (pintype "passive"))
      (node (ref "C11") (pin "+") (pinfunction "+_+") (pintype "passive"))
      (node (ref "C12") (pin "+") (pinfunction "+_+") (pintype "passive"))
      (node (ref "C13") (pin "1") (pinfunction "1_1") (pintype "passive"))
      (node (ref "C14") (pin "1") (pinfunction "1_1") (pintype "passive"))
      (node (ref "C15") (pin "+") (pinfunction "+_+") (pintype "passive"))
      (node (ref "C16") (pin "1") (pinfunction "1_1") (pintype "passive"))
      (node (ref "C17") (pin "1") (pinfunction "1_1") (pintype "passive"))
      (node (ref "C18") (pin "+") (pinfunction "+_+") (pintype "passive"))
      (node (ref "C19") (pin "+") (pinfunction "+_+") (pintype "passive"))
      (node (ref "C20") (pin "+") (pinfunction "+_+") (pintype "passive"))
      (node (ref "C21") (pin "1") (pinfunction "1_1") (pintype "passive"))
      (node (ref "C22") (pin "+") (pinfunction "+_+") (pintype "passive"))
      (node (ref "C23") (pin "1") (pinfunction "1_1") (pintype "passive"))
      (node (ref "C25") (pin "1") (pinfunction "1_1") (pintype "passive"))
      (node (ref "C26") (pin "1") (pinfunction "1_1") (pintype "passive"))
      (node (ref "C27") (pin "1") (pinfunction "1_1") (pintype "passive"))
      (node (ref "C29") (pin "1") (pinfunction "1_1") (pintype "passive"))
      (node (ref "C31") (pin "1") (pinfunction "1_1") (pintype "passive"))
      (node (ref "C32") (pin "1") (pinfunction "1_1") (pintype "passive"))
      (node (ref "C34") (pin "1") (pinfunction "1_1") (pintype "passive"))
      (node (ref "C36") (pin "1") (pinfunction "1_1") (pintype "passive"))
      (node (ref "C37") (pin "1") (pinfunction "1_1") (pintype "passive"))
      (node (ref "C38") (pin "1") (pinfunction "1_1") (pintype "passive"))
      (node (ref "C39") (pin "1") (pinfunction "1_1") (pintype "passive"))
      (node (ref "C4") (pin "+") (pinfunction "+_+") (pintype "passive"))
      (node (ref "C40") (pin "1") (pinfunction "1_1") (pintype "passive"))
      (node (ref "C41") (pin "1") (pinfunction "1_1") (pintype "passive"))
      (node (ref "C42") (pin "1") (pinfunction "1_1") (pintype "passive"))
      (node (ref "C45") (pin "1") (pinfunction "1_1") (pintype "passive"))
      (node (ref "C46") (pin "1") (pinfunction "1_1") (pintype "passive"))
      (node (ref "C47") (pin "1") (pinfunction "1_1") (pintype "passive"))
      (node (ref "C48") (pin "1") (pinfunction "1_1") (pintype "passive"))
      (node (ref "C51") (pin "1") (pinfunction "1_1") (pintype "passive"))
      (node (ref "C53") (pin "1") (pinfunction "1_1") (pintype "passive"))
      (node (ref "C58") (pin "2") (pinfunction "2_2") (pintype "passive"))
      (node (ref "C6") (pin "1") (pinfunction "1_1") (pintype "passive"))
      (node (ref "C60") (pin "2") (pinfunction "2_2") (pintype "passive"))
      (node (ref "C62") (pin "2") (pinfunction "2_2") (pintype "passive"))
      (node (ref "C64") (pin "2") (pinfunction "2_2") (pintype "passive"))
      (node (ref "C65") (pin "2") (pinfunction "2_2") (pintype "passive"))
      (node (ref "C7") (pin "+") (pinfunction "+_+") (pintype "passive"))
      (node (ref "C9") (pin "+") (pinfunction "+_+") (pintype "passive"))
      (node (ref "CON1") (pin "13") (pinfunction "VCC2_13") (pintype "power_in"))
      (node (ref "CON1") (pin "36") (pinfunction "/WE_36") (pintype "input"))
      (node (ref "CON1") (pin "38") (pinfunction "VCC1_38") (pintype "power_in"))
      (node (ref "D1") (pin "2") (pinfunction "C_2") (pintype "passive"))
      (node (ref "D2") (pin "2") (pinfunction "C_2") (pintype "passive"))
      (node (ref "D3") (pin "2") (pinfunction "C_2") (pintype "passive"))
      (node (ref "D4") (pin "2") (pinfunction "C_2") (pintype "passive"))
      (node (ref "IC10") (pin "2") (pinfunction "OUT_2") (pintype "power_in"))
      (node (ref "IC10") (pin "4") (pinfunction "OUT_4") (pintype "power_in"))
      (node (ref "IC11") (pin "16") (pinfunction "VCC_16") (pintype "power_in"))
      (node (ref "IC12") (pin "15") (pinfunction "VDDTX_15") (pintype "input"))
      (node (ref "IC12") (pin "19") (pinfunction "VDDRX_19") (pintype "input"))
      (node (ref "IC12") (pin "20") (pinfunction "VDDPLL_20") (pintype "input"))
      (node (ref "IC12") (pin "25") (pinfunction "VDDOSC_25") (pintype "input"))
      (node (ref "IC12") (pin "28") (pinfunction "VDD_28") (pintype "input"))
      (node (ref "IC13") (pin "4") (pinfunction "IN_4") (pintype "power_in"))
      (node (ref "IC6") (pin "26") (pinfunction "VCCIO_26") (pintype "power_in"))
      (node (ref "IC7") (pin "107") (pinfunction "VCCIO3_107") (pintype "power_in"))
      (node (ref "IC7") (pin "117") (pinfunction "VCCIO3_117") (pintype "power_in"))
      (node (ref "IC7") (pin "130") (pinfunction "VCCJ_130") (pintype "power_in"))
      (node (ref "IC7") (pin "132") (pinfunction "VCCAUX_132") (pintype "power_in"))
      (node (ref "IC7") (pin "141") (pinfunction "VCCIO2_141") (pintype "power_in"))
      (node (ref "IC7") (pin "152") (pinfunction "VCCIO2_152") (pintype "power_in"))
      (node (ref "IC7") (pin "16") (pinfunction "VCCIO7_16") (pintype "power_in"))
      (node (ref "IC7") (pin "166") (pinfunction "VCCIO1_166") (pintype "power_in"))
      (node (ref "IC7") (pin "172") (pinfunction "VCCIO1_172") (pintype "power_in"))
      (node (ref "IC7") (pin "181") (pinfunction "VCCAUX_181") (pintype "power_in"))
      (node (ref "IC7") (pin "191") (pinfunction "VCCIO0_191") (pintype "power_in"))
      (node (ref "IC7") (pin "200") (pinfunction "VCCIO0_200") (pintype "power_in"))
      (node (ref "IC7") (pin "204") (pinfunction "ULC_VCCPLL_204") (pintype "power_in"))
      (node (ref "IC7") (pin "25") (pinfunction "VCCAUX_25") (pintype "power_in"))
      (node (ref "IC7") (pin "29") (pinfunction "CFG0_29") (pintype "input"))
      (node (ref "IC7") (pin "38") (pinfunction "VCCIO6_38") (pintype "power_in"))
      (node (ref "IC7") (pin "5") (pinfunction "VCCIO7_5") (pintype "power_in"))
      (node (ref "IC7") (pin "50") (pinfunction "VCCIO6_50") (pintype "power_in"))
      (node (ref "IC7") (pin "61") (pinfunction "VCCIO5_61") (pintype "power_in"))
      (node (ref "IC7") (pin "70") (pinfunction "VCCIO5_70") (pintype "power_in"))
      (node (ref "IC7") (pin "80") (pinfunction "VCCAUX_80") (pintype "power_in"))
      (node (ref "IC7") (pin "89") (pinfunction "VCCIO4_89") (pintype "power_in"))
      (node (ref "IC7") (pin "95") (pinfunction "VCCIO4_95") (pintype "power_in"))
      (node (ref "IC7") (pin "99") (pinfunction "LRC_VCCPLL_99") (pintype "power_in"))
      (node (ref "IC8") (pin "11") (pinfunction "VCC_11") (pintype "power_in"))
      (node (ref "IC8") (pin "33") (pinfunction "VCC2_33") (pintype "power_in"))
      (node (ref "IC9") (pin "11") (pinfunction "VCC_11") (pintype "power_in"))
      (node (ref "IC9") (pin "33") (pinfunction "VCC2_33") (pintype "power_in"))
      (node (ref "J2") (pin "4") (pinfunction "4_4") (pintype "input"))
      (node (ref "L1") (pin "1") (pinfunction "1_1") (pintype "passive"))
      (node (ref "LED2") (pin "A") (pinfunction "A_A") (pintype "passive"))
      (node (ref "LED3") (pin "A") (pinfunction "A_A") (pintype "passive"))
      (node (ref "QG1") (pin "1") (pinfunction "EN_1") (pintype "passive"))
      (node (ref "QG1") (pin "8") (pinfunction "VCC_8") (pintype "power_in"))
      (node (ref "R10") (pin "2") (pinfunction "2_2") (pintype "passive"))
      (node (ref "R11") (pin "2") (pinfunction "2_2") (pintype "passive"))
      (node (ref "R12") (pin "2") (pinfunction "2_2") (pintype "passive"))
      (node (ref "R13") (pin "2") (pinfunction "2_2") (pintype "passive"))
      (node (ref "R14") (pin "2") (pinfunction "2_2") (pintype "passive"))
      (node (ref "R15") (pin "2") (pinfunction "2_2") (pintype "passive"))
      (node (ref "R16") (pin "2") (pinfunction "2_2") (pintype "passive"))
      (node (ref "R7") (pin "2") (pinfunction "2_2") (pintype "passive"))
      (node (ref "R9") (pin "2") (pinfunction "2_2") (pintype "passive"))
      (node (ref "SV1") (pin "1") (pinfunction "1_1") (pintype "passive"))
      (node (ref "SV2") (pin "6") (pinfunction "6_6") (pintype "passive"))
    )
    (net (code "290") (name "VCCINT") (class "Default")
      (node (ref "C10") (pin "1") (pinfunction "1_1") (pintype "passive"))
      (node (ref "C2") (pin "1") (pinfunction "1_1") (pintype "passive"))
      (node (ref "C24") (pin "+") (pinfunction "+_+") (pintype "passive"))
      (node (ref "C3") (pin "1") (pinfunction "1_1") (pintype "passive"))
      (node (ref "C43") (pin "1") (pinfunction "1_1") (pintype "passive"))
      (node (ref "C44") (pin "1") (pinfunction "1_1") (pintype "passive"))
      (node (ref "C5") (pin "1") (pinfunction "1_1") (pintype "passive"))
      (node (ref "C8") (pin "1") (pinfunction "1_1") (pintype "passive"))
      (node (ref "IC13") (pin "1") (pinfunction "OUT_1") (pintype "power_in"))
      (node (ref "IC7") (pin "108") (pinfunction "VCC_108") (pintype "power_in"))
      (node (ref "IC7") (pin "131") (pinfunction "VCC_131") (pintype "power_in"))
      (node (ref "IC7") (pin "153") (pinfunction "VCC_153") (pintype "power_in"))
      (node (ref "IC7") (pin "182") (pinfunction "VCC_182") (pintype "power_in"))
      (node (ref "IC7") (pin "26") (pinfunction "VCC_26") (pintype "power_in"))
      (node (ref "IC7") (pin "27") (pinfunction "VCC_27") (pintype "power_in"))
      (node (ref "IC7") (pin "4") (pinfunction "VCC_4") (pintype "power_in"))
      (node (ref "IC7") (pin "49") (pinfunction "VCC_49") (pintype "power_in"))
      (node (ref "IC7") (pin "79") (pinfunction "VCC_79") (pintype "power_in"))
    )
    (net (code "291") (name "VGA_BL0") (class "Default")
      (node (ref "IC7") (pin "33") (pinfunction "PL19B_33") (pintype "bidirectional"))
      (node (ref "R30") (pin "1") (pinfunction "1_1") (pintype "passive"))
    )
    (net (code "292") (name "VGA_BL1") (class "Default")
      (node (ref "IC7") (pin "34") (pinfunction "PL20A_34") (pintype "bidirectional"))
      (node (ref "R29") (pin "1") (pinfunction "1_1") (pintype "passive"))
    )
    (net (code "293") (name "VGA_BL2") (class "Default")
      (node (ref "IC7") (pin "35") (pinfunction "PL20B_35") (pintype "bidirectional"))
      (node (ref "R28") (pin "1") (pinfunction "1_1") (pintype "passive"))
    )
    (net (code "294") (name "VGA_GR0") (class "Default")
      (node (ref "IC7") (pin "36") (pinfunction "PL21A_36") (pintype "bidirectional"))
      (node (ref "R27") (pin "1") (pinfunction "1_1") (pintype "passive"))
    )
    (net (code "295") (name "VGA_GR1") (class "Default")
      (node (ref "IC7") (pin "39") (pinfunction "PL21B_39") (pintype "bidirectional"))
      (node (ref "R26") (pin "1") (pinfunction "1_1") (pintype "passive"))
    )
    (net (code "296") (name "VGA_GR2") (class "Default")
      (node (ref "IC7") (pin "40") (pinfunction "PL23A_40") (pintype "bidirectional"))
      (node (ref "R25") (pin "1") (pinfunction "1_1") (pintype "passive"))
    )
    (net (code "297") (name "VGA_HSYNC") (class "Default")
      (node (ref "IC7") (pin "23") (pinfunction "PL16B_23") (pintype "bidirectional"))
      (node (ref "R32") (pin "2") (pinfunction "2_2") (pintype "passive"))
    )
    (net (code "298") (name "VGA_RD0") (class "Default")
      (node (ref "IC7") (pin "41") (pinfunction "PL22A_41") (pintype "bidirectional"))
      (node (ref "R24") (pin "1") (pinfunction "1_1") (pintype "passive"))
    )
    (net (code "299") (name "VGA_RD1") (class "Default")
      (node (ref "IC7") (pin "42") (pinfunction "PL23B_42") (pintype "bidirectional"))
      (node (ref "R23") (pin "1") (pinfunction "1_1") (pintype "passive"))
    )
    (net (code "300") (name "VGA_RD2") (class "Default")
      (node (ref "IC7") (pin "43") (pinfunction "PL22B_43") (pintype "bidirectional"))
      (node (ref "R22") (pin "1") (pinfunction "1_1") (pintype "passive"))
    )
    (net (code "301") (name "VGA_VSYNC") (class "Default")
      (node (ref "IC7") (pin "19") (pinfunction "PL14B_19") (pintype "bidirectional"))
      (node (ref "R31") (pin "2") (pinfunction "2_2") (pintype "passive"))
    )
    (net (code "302") (name "unconnected-(IC12-NC*-Pad5)") (class "Default")
      (node (ref "IC12") (pin "5") (pinfunction "NC*_5") (pintype "output"))
    )
    (net (code "303") (name "unconnected-(J1-PadA13)") (class "Default")
      (node (ref "J1") (pin "A13") (pinfunction "A13_A13") (pintype "passive"))
    )
    (net (code "304") (name "unconnected-(J1-PadA20)") (class "Default")
      (node (ref "J1") (pin "A20") (pinfunction "A20_A20") (pintype "passive"))
    )
    (net (code "305") (name "unconnected-(J1-PadA21)") (class "Default")
      (node (ref "J1") (pin "A21") (pinfunction "A21_A21") (pintype "passive"))
    )
    (net (code "306") (name "unconnected-(J1-PadA28)") (class "Default")
      (node (ref "J1") (pin "A28") (pinfunction "A28_A28") (pintype "passive"))
    )
    (net (code "307") (name "unconnected-(J1-PadC13)") (class "Default")
      (node (ref "J1") (pin "C13") (pinfunction "C13_C13") (pintype "passive"))
    )
    (net (code "308") (name "unconnected-(J1-PadC23)") (class "Default")
      (node (ref "J1") (pin "C23") (pinfunction "C23_C23") (pintype "passive"))
    )
    (net (code "309") (name "unconnected-(J1-PadC26)") (class "Default")
      (node (ref "J1") (pin "C26") (pinfunction "C26_C26") (pintype "passive"))
    )
    (net (code "310") (name "unconnected-(J1-PadC29)") (class "Default")
      (node (ref "J1") (pin "C29") (pinfunction "C29_C29") (pintype "passive"))
    )
    (net (code "311") (name "unconnected-(J3-Pad4)") (class "Default")
      (node (ref "J3") (pin "4") (pinfunction "4_4") (pintype "passive"))
    )
    (net (code "312") (name "unconnected-(J3-Pad5)") (class "Default")
      (node (ref "J3") (pin "5") (pinfunction "5_5") (pintype "passive"))
    )
    (net (code "313") (name "unconnected-(J3-Pad9)") (class "Default")
      (node (ref "J3") (pin "9") (pinfunction "9_9") (pintype "passive"))
    )
    (net (code "314") (name "unconnected-(J3-Pad15)") (class "Default")
      (node (ref "J3") (pin "15") (pinfunction "15_15") (pintype "passive"))
    )
    (net (code "315") (name "unconnected-(J3G-2-Pad1-2)") (class "Default")
      (node (ref "J3") (pin "1-2") (pinfunction "2_1-2") (pintype "passive"))
    )
    (net (code "316") (name "unconnected-(J3G-6-Pad1-6)") (class "Default")
      (node (ref "J3") (pin "1-6") (pinfunction "6_1-6") (pintype "passive"))
    )
    (net (code "317") (name "unconnected-(J3H-2-Pad2-2)") (class "Default")
      (node (ref "J3") (pin "2-2") (pinfunction "2_2-2") (pintype "passive"))
    )
    (net (code "318") (name "unconnected-(J3H-6-Pad2-6)") (class "Default")
      (node (ref "J3") (pin "2-6") (pinfunction "6_2-6") (pintype "passive"))
    )
    (net (code "319") (name "unconnected-(J4-RCT-Pad6)") (class "Default")
      (node (ref "J4") (pin "6") (pinfunction "RCT_6") (pintype "passive"))
    )
    (net (code "320") (name "unconnected-(JP18-Pad1)") (class "Default")
      (node (ref "JP18") (pin "1") (pinfunction "1_1") (pintype "passive"))
    )
    (net (code "321") (name "unconnected-(JP18-Pad4)") (class "Default")
      (node (ref "JP18") (pin "4") (pinfunction "4_4") (pintype "passive"))
    )
    (net (code "322") (name "unconnected-(JP18-Pad6)") (class "Default")
      (node (ref "JP18") (pin "6") (pinfunction "6_6") (pintype "passive"))
    )
    (net (code "323") (name "unconnected-(JP18-Pad9)") (class "Default")
      (node (ref "JP18") (pin "9") (pinfunction "9_9") (pintype "passive"))
    )
    (net (code "324") (name "unconnected-(JP18-Pad10)") (class "Default")
      (node (ref "JP18") (pin "10") (pinfunction "10_10") (pintype "passive"))
    )
    (net (code "325") (name "unconnected-(SV2-Pad9)") (class "Default")
      (node (ref "SV2") (pin "9") (pinfunction "9_9") (pintype "passive"))
    )
    (net (code "326") (name "unconnected-(SV2-Pad10)") (class "Default")
      (node (ref "SV2") (pin "10") (pinfunction "10_10") (pintype "passive"))
    )
    (net (code "327") (name "unconnected-(X1A-S-Pad1)") (class "Default")
      (node (ref "X1") (pin "1") (pinfunction "S_1") (pintype "passive"))
    )
    (net (code "328") (name "unconnected-(X1AG-S-Pad39)") (class "Default")
      (node (ref "X1") (pin "39") (pinfunction "S_39") (pintype "passive"))
    )
    (net (code "329") (name "unconnected-(X1M-S-Pad20)") (class "Default")
      (node (ref "X1") (pin "20") (pinfunction "S_20") (pintype "passive"))
    )
    (net (code "330") (name "unconnected-(X2-Pad3)") (class "Default")
      (node (ref "X2") (pin "3") (pinfunction "3_3") (pintype "passive"))
    )
    (net (code "331") (name "unconnected-(X2-Pad4)") (class "Default")
      (node (ref "X2") (pin "4") (pinfunction "4_4") (pintype "passive"))
    )
    (net (code "332") (name "{slash}BUSACK") (class "Default")
      (node (ref "J1") (pin "A31") (pinfunction "A31_A31") (pintype "passive"))
    )
    (net (code "333") (name "{slash}BUSRQ") (class "Default")
      (node (ref "J1") (pin "A11") (pinfunction "A11_A11") (pintype "passive"))
    )
    (net (code "334") (name "{slash}HALT") (class "Default")
      (node (ref "J1") (pin "C25") (pinfunction "C25_C25") (pintype "passive"))
    )
    (net (code "335") (name "{slash}INT") (class "Default")
      (node (ref "IC6") (pin "2") (pinfunction "1/6_2") (pintype "bidirectional"))
      (node (ref "J1") (pin "C21") (pinfunction "C21_C21") (pintype "passive"))
      (node (ref "R2") (pin "1") (pinfunction "1_1") (pintype "passive"))
    )
    (net (code "336") (name "{slash}NMI") (class "Default")
      (node (ref "IC6") (pin "44") (pinfunction "1/5_44") (pintype "bidirectional"))
      (node (ref "J1") (pin "C20") (pinfunction "C20_C20") (pintype "passive"))
      (node (ref "R1") (pin "1") (pinfunction "1_1") (pintype "passive"))
    )
    (net (code "337") (name "{slash}WAIT") (class "Default")
      (node (ref "IC6") (pin "37") (pinfunction "2/4_37") (pintype "bidirectional"))
      (node (ref "J1") (pin "A10") (pinfunction "A10_A10") (pintype "passive"))
      (node (ref "R3") (pin "1") (pinfunction "1_1") (pintype "passive"))
    )
  )
)
